# OPLSniffer.net
KiCad netlist of a schematic drawn in EAGLE
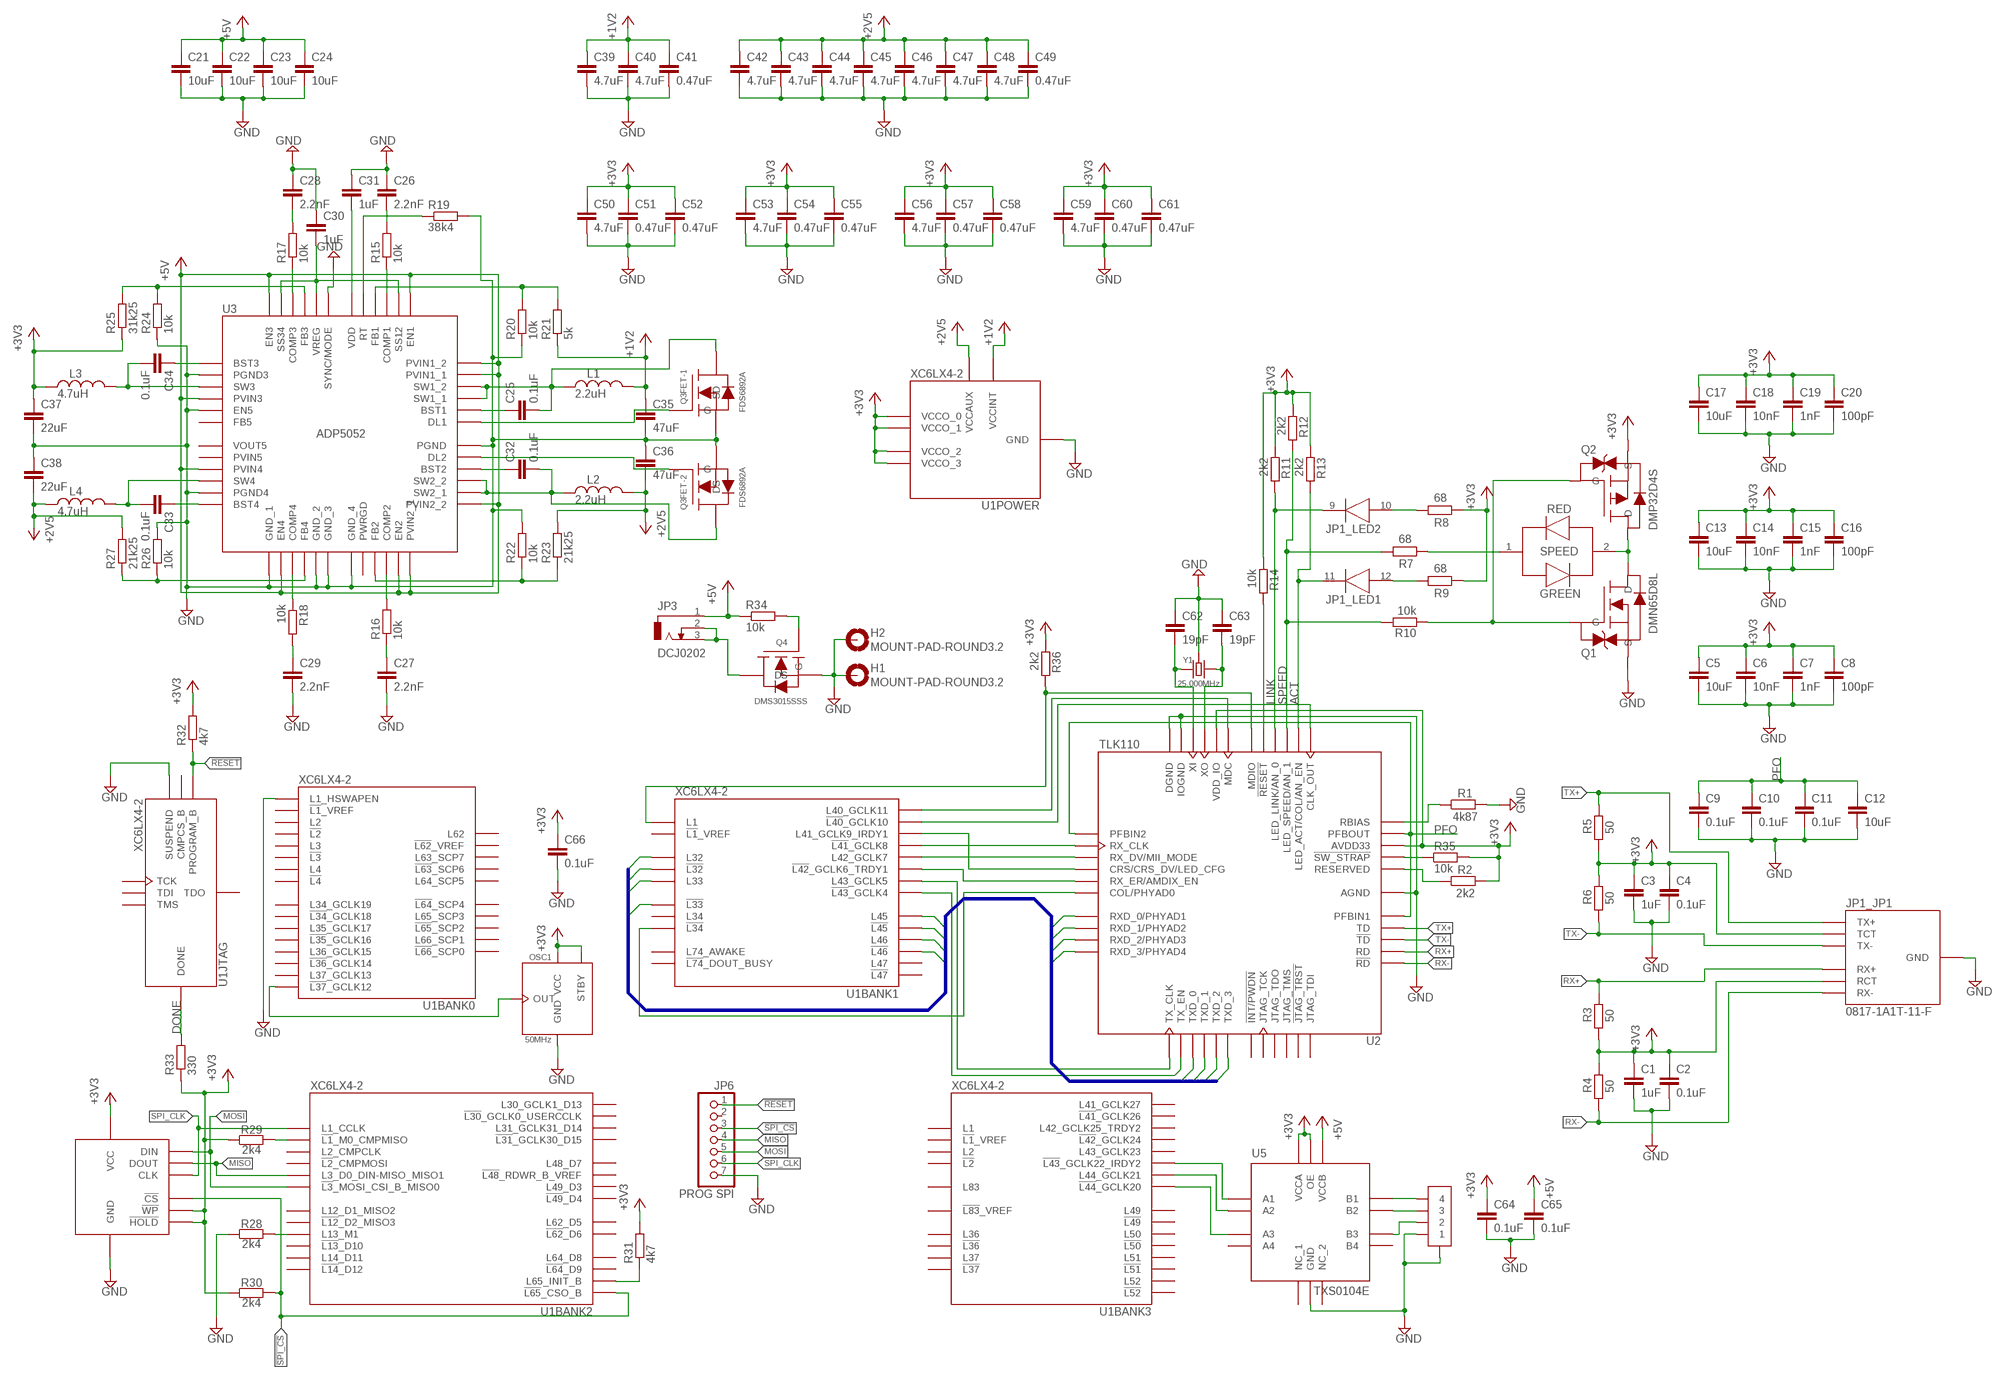
[diagram p0: schematic, sheet 1]

(export (version "E")
  (design (tool "Eeschema 10.0.6"))
  (components
    (comp (ref "C1")
      (value "1uF")
      (footprint "eagle-import:C0603K")
      (fields (field (name "MPN") "MC0603X105M6R3CT"))
      (libsource (lib "eagle-import") (part "C-EUC0603K"))
    )
    (comp (ref "C2")
      (value "0.1uF")
      (footprint "eagle-import:C0603K")
      (fields (field (name "MPN") "MC0603B104J250CT"))
      (libsource (lib "eagle-import") (part "C-EUC0603K"))
    )
    (comp (ref "C3")
      (value "1uF")
      (footprint "eagle-import:C0603K")
      (fields (field (name "MPN") "MC0603X105M6R3CT"))
      (libsource (lib "eagle-import") (part "C-EUC0603K"))
    )
    (comp (ref "C4")
      (value "0.1uF")
      (footprint "eagle-import:C0603K")
      (fields (field (name "MPN") "MC0603B104J250CT"))
      (libsource (lib "eagle-import") (part "C-EUC0603K"))
    )
    (comp (ref "C5")
      (value "10uF")
      (footprint "eagle-import:C0805K")
      (fields (field (name "MPN") "MC0805X106K250CT"))
      (libsource (lib "eagle-import") (part "C-EUC0805K"))
    )
    (comp (ref "C6")
      (value "10nF")
      (footprint "eagle-import:C0603K")
      (fields (field (name "MPN") "MCCA000238"))
      (libsource (lib "eagle-import") (part "C-EUC0603K"))
    )
    (comp (ref "C7")
      (value "1nF")
      (footprint "eagle-import:C0603K")
      (fields (field (name "MPN") "MC0603B102K500CT"))
      (libsource (lib "eagle-import") (part "C-EUC0603K"))
    )
    (comp (ref "C8")
      (value "100pF")
      (footprint "eagle-import:C0603K")
      (fields (field (name "MPN") "MCCA001175"))
      (libsource (lib "eagle-import") (part "C-EUC0603K"))
    )
    (comp (ref "C9")
      (value "0.1uF")
      (footprint "eagle-import:C0603K")
      (fields (field (name "MPN") "MC0603B104J250CT"))
      (libsource (lib "eagle-import") (part "C-EUC0603K"))
    )
    (comp (ref "C10")
      (value "0.1uF")
      (footprint "eagle-import:C0603K")
      (fields (field (name "MPN") "MC0603B104J250CT"))
      (libsource (lib "eagle-import") (part "C-EUC0603K"))
    )
    (comp (ref "C11")
      (value "0.1uF")
      (footprint "eagle-import:C0603K")
      (fields (field (name "MPN") "MC0603B104J250CT"))
      (libsource (lib "eagle-import") (part "C-EUC0603K"))
    )
    (comp (ref "C12")
      (value "10uF")
      (footprint "eagle-import:C0805K")
      (fields (field (name "MPN") "MC0805X106K250CT"))
      (libsource (lib "eagle-import") (part "C-EUC0805K"))
    )
    (comp (ref "C13")
      (value "10uF")
      (footprint "eagle-import:C0805K")
      (fields (field (name "MPN") "MC0805X106K250CT"))
      (libsource (lib "eagle-import") (part "C-EUC0805K"))
    )
    (comp (ref "C14")
      (value "10nF")
      (footprint "eagle-import:C0603K")
      (fields (field (name "MPN") "MCCA000238"))
      (libsource (lib "eagle-import") (part "C-EUC0603K"))
    )
    (comp (ref "C15")
      (value "1nF")
      (footprint "eagle-import:C0603K")
      (fields (field (name "MPN") "MC0603B102K500CT"))
      (libsource (lib "eagle-import") (part "C-EUC0603K"))
    )
    (comp (ref "C16")
      (value "100pF")
      (footprint "eagle-import:C0603K")
      (fields (field (name "MPN") "MCCA001175"))
      (libsource (lib "eagle-import") (part "C-EUC0603K"))
    )
    (comp (ref "C17")
      (value "10uF")
      (footprint "eagle-import:C0805K")
      (fields (field (name "MPN") "MC0805X106K250CT"))
      (libsource (lib "eagle-import") (part "C-EUC0805K"))
    )
    (comp (ref "C18")
      (value "10nF")
      (footprint "eagle-import:C0603K")
      (fields (field (name "MPN") "MCCA000238"))
      (libsource (lib "eagle-import") (part "C-EUC0603K"))
    )
    (comp (ref "C19")
      (value "1nF")
      (footprint "eagle-import:C0603K")
      (fields (field (name "MPN") "MC0603B102K500CT"))
      (libsource (lib "eagle-import") (part "C-EUC0603K"))
    )
    (comp (ref "C20")
      (value "100pF")
      (footprint "eagle-import:C0603K")
      (fields (field (name "MPN") "MCCA001175"))
      (libsource (lib "eagle-import") (part "C-EUC0603K"))
    )
    (comp (ref "C21")
      (value "10uF")
      (footprint "eagle-import:C0805K")
      (fields (field (name "MPN") "GRM21BR61E106KA73L"))
      (libsource (lib "eagle-import") (part "C-EUC0805K"))
    )
    (comp (ref "C22")
      (value "10uF")
      (footprint "eagle-import:C0805K")
      (fields (field (name "MPN") "MC0805X106K250CT"))
      (libsource (lib "eagle-import") (part "C-EUC0805K"))
    )
    (comp (ref "C23")
      (value "10uF")
      (footprint "eagle-import:C0805K")
      (fields (field (name "MPN") "MC0805X106K250CT"))
      (libsource (lib "eagle-import") (part "C-EUC0805K"))
    )
    (comp (ref "C24")
      (value "10uF")
      (footprint "eagle-import:C0805K")
      (fields (field (name "MPN") "MC0805X106K250CT"))
      (libsource (lib "eagle-import") (part "C-EUC0805K"))
    )
    (comp (ref "C25")
      (value "0.1uF")
      (footprint "eagle-import:C0603K")
      (fields (field (name "MPN") "MC0603B104J250CT"))
      (libsource (lib "eagle-import") (part "C-EUC0603K"))
    )
    (comp (ref "C26")
      (value "2.2nF")
      (footprint "eagle-import:C0603K")
      (fields (field (name "MPN") "MCCA001160"))
      (libsource (lib "eagle-import") (part "C-EUC0603K"))
    )
    (comp (ref "C27")
      (value "2.2nF")
      (footprint "eagle-import:C0603K")
      (fields (field (name "MPN") "MCCA001160"))
      (libsource (lib "eagle-import") (part "C-EUC0603K"))
    )
    (comp (ref "C28")
      (value "2.2nF")
      (footprint "eagle-import:C0603K")
      (fields (field (name "MPN") "MCCA001160"))
      (libsource (lib "eagle-import") (part "C-EUC0603K"))
    )
    (comp (ref "C29")
      (value "2.2nF")
      (footprint "eagle-import:C0603K")
      (fields (field (name "MPN") "MCCA001160"))
      (libsource (lib "eagle-import") (part "C-EUC0603K"))
    )
    (comp (ref "C30")
      (value "1uF")
      (footprint "eagle-import:C0603K")
      (fields (field (name "MPN") "MC0603X105M6R3CT"))
      (libsource (lib "eagle-import") (part "C-EUC0603K"))
    )
    (comp (ref "C31")
      (value "1uF")
      (footprint "eagle-import:C0603K")
      (fields (field (name "MPN") "MC0603X105M6R3CT"))
      (libsource (lib "eagle-import") (part "C-EUC0603K"))
    )
    (comp (ref "C32")
      (value "0.1uF")
      (footprint "eagle-import:C0603K")
      (fields (field (name "MPN") "MC0603B104J250CT"))
      (libsource (lib "eagle-import") (part "C-EUC0603K"))
    )
    (comp (ref "C33")
      (value "0.1uF")
      (footprint "eagle-import:C0603K")
      (fields (field (name "MPN") "MC0603B104J250CT"))
      (libsource (lib "eagle-import") (part "C-EUC0603K"))
    )
    (comp (ref "C34")
      (value "0.1uF")
      (footprint "eagle-import:C0603K")
      (fields (field (name "MPN") "MC0603B104J250CT"))
      (libsource (lib "eagle-import") (part "C-EUC0603K"))
    )
    (comp (ref "C35")
      (value "47uF")
      (footprint "eagle-import:C1206K")
      (fields (field (name "MPN") "GRM31CR60J476KE19L"))
      (libsource (lib "eagle-import") (part "C-EUC1206K"))
    )
    (comp (ref "C36")
      (value "47uF")
      (footprint "eagle-import:C1206K")
      (fields (field (name "MPN") "GRM31CR60J476KE19L"))
      (libsource (lib "eagle-import") (part "C-EUC1206K"))
    )
    (comp (ref "C37")
      (value "22uF")
      (footprint "eagle-import:C0805K")
      (fields (field (name "MPN") "C0805C226M9PACTU"))
      (libsource (lib "eagle-import") (part "C-EUC0805K"))
    )
    (comp (ref "C38")
      (value "22uF")
      (footprint "eagle-import:C0805K")
      (fields (field (name "MPN") "C0805C226M9PACTU"))
      (libsource (lib "eagle-import") (part "C-EUC0805K"))
    )
    (comp (ref "C39")
      (value "4.7uF")
      (footprint "eagle-import:C0603K")
      (fields (field (name "MPN") "MC0603X475K6R3CT"))
      (libsource (lib "eagle-import") (part "C-EUC0603K"))
    )
    (comp (ref "C40")
      (value "4.7uF")
      (footprint "eagle-import:C0603K")
      (fields (field (name "MPN") "MC0603X475K6R3CT"))
      (libsource (lib "eagle-import") (part "C-EUC0603K"))
    )
    (comp (ref "C41")
      (value "0.47uF")
      (footprint "eagle-import:C0603K")
      (fields (field (name "MPN") "MC0603X474K100CT"))
      (libsource (lib "eagle-import") (part "C-EUC0603K"))
    )
    (comp (ref "C42")
      (value "4.7uF")
      (footprint "eagle-import:C0603K")
      (fields (field (name "MPN") "MC0603X475K6R3CT"))
      (libsource (lib "eagle-import") (part "C-EUC0603K"))
    )
    (comp (ref "C43")
      (value "4.7uF")
      (footprint "eagle-import:C0603K")
      (fields (field (name "MPN") "MC0603X475K6R3CT"))
      (libsource (lib "eagle-import") (part "C-EUC0603K"))
    )
    (comp (ref "C44")
      (value "4.7uF")
      (footprint "eagle-import:C0603K")
      (fields (field (name "MPN") "MC0603X475K6R3CT"))
      (libsource (lib "eagle-import") (part "C-EUC0603K"))
    )
    (comp (ref "C45")
      (value "4.7uF")
      (footprint "eagle-import:C0603K")
      (fields (field (name "MPN") "MC0603X475K6R3CT"))
      (libsource (lib "eagle-import") (part "C-EUC0603K"))
    )
    (comp (ref "C46")
      (value "4.7uF")
      (footprint "eagle-import:C0603K")
      (fields (field (name "MPN") "MC0603X475K6R3CT"))
      (libsource (lib "eagle-import") (part "C-EUC0603K"))
    )
    (comp (ref "C47")
      (value "4.7uF")
      (footprint "eagle-import:C0603K")
      (fields (field (name "MPN") "MC0603X475K6R3CT"))
      (libsource (lib "eagle-import") (part "C-EUC0603K"))
    )
    (comp (ref "C48")
      (value "4.7uF")
      (footprint "eagle-import:C0603K")
      (fields (field (name "MPN") "MC0603X475K6R3CT"))
      (libsource (lib "eagle-import") (part "C-EUC0603K"))
    )
    (comp (ref "C49")
      (value "0.47uF")
      (footprint "eagle-import:C0603K")
      (fields (field (name "MPN") "MC0603X474K100CT"))
      (libsource (lib "eagle-import") (part "C-EUC0603K"))
    )
    (comp (ref "C50")
      (value "4.7uF")
      (footprint "eagle-import:C0603K")
      (fields (field (name "MPN") "MC0603X475K6R3CT"))
      (libsource (lib "eagle-import") (part "C-EUC0603K"))
    )
    (comp (ref "C51")
      (value "0.47uF")
      (footprint "eagle-import:C0603K")
      (fields (field (name "MPN") "MC0603X474K100CT"))
      (libsource (lib "eagle-import") (part "C-EUC0603K"))
    )
    (comp (ref "C52")
      (value "0.47uF")
      (footprint "eagle-import:C0603K")
      (fields (field (name "MPN") "MC0603X474K100CT"))
      (libsource (lib "eagle-import") (part "C-EUC0603K"))
    )
    (comp (ref "C53")
      (value "4.7uF")
      (footprint "eagle-import:C0603K")
      (fields (field (name "MPN") "MC0603X475K6R3CT"))
      (libsource (lib "eagle-import") (part "C-EUC0603K"))
    )
    (comp (ref "C54")
      (value "0.47uF")
      (footprint "eagle-import:C0603K")
      (fields (field (name "MPN") "MC0603X474K100CT"))
      (libsource (lib "eagle-import") (part "C-EUC0603K"))
    )
    (comp (ref "C55")
      (value "0.47uF")
      (footprint "eagle-import:C0603K")
      (fields (field (name "MPN") "MC0603X474K100CT"))
      (libsource (lib "eagle-import") (part "C-EUC0603K"))
    )
    (comp (ref "C56")
      (value "4.7uF")
      (footprint "eagle-import:C0603K")
      (fields (field (name "MPN") "MC0603X475K6R3CT"))
      (libsource (lib "eagle-import") (part "C-EUC0603K"))
    )
    (comp (ref "C57")
      (value "0.47uF")
      (footprint "eagle-import:C0603K")
      (fields (field (name "MPN") "MC0603X474K100CT"))
      (libsource (lib "eagle-import") (part "C-EUC0603K"))
    )
    (comp (ref "C58")
      (value "0.47uF")
      (footprint "eagle-import:C0603K")
      (fields (field (name "MPN") "MC0603X474K100CT"))
      (libsource (lib "eagle-import") (part "C-EUC0603K"))
    )
    (comp (ref "C59")
      (value "4.7uF")
      (footprint "eagle-import:C0603K")
      (fields (field (name "MPN") "MC0603X475K6R3CT"))
      (libsource (lib "eagle-import") (part "C-EUC0603K"))
    )
    (comp (ref "C60")
      (value "0.47uF")
      (footprint "eagle-import:C0603K")
      (fields (field (name "MPN") "MC0603X474K100CT"))
      (libsource (lib "eagle-import") (part "C-EUC0603K"))
    )
    (comp (ref "C61")
      (value "0.47uF")
      (footprint "eagle-import:C0603K")
      (fields (field (name "MPN") "MC0603X474K100CT"))
      (libsource (lib "eagle-import") (part "C-EUC0603K"))
    )
    (comp (ref "C62")
      (value "19pF")
      (footprint "eagle-import:C0603K")
      (fields (field (name "MFR") "Kemet") (field (name "MPN") "C0603C180J5GACTU"))
      (libsource (lib "eagle-import") (part "C-EUC0603K"))
    )
    (comp (ref "C63")
      (value "19pF")
      (footprint "eagle-import:C0603K")
      (fields (field (name "MFR") "Kemet") (field (name "MPN") "C0603C180J5GACTU"))
      (libsource (lib "eagle-import") (part "C-EUC0603K"))
    )
    (comp (ref "C64")
      (value "0.1uF")
      (footprint "eagle-import:C0603K")
      (fields (field (name "MPN") "MC0603B104J250CT"))
      (libsource (lib "eagle-import") (part "C-EUC0603K"))
    )
    (comp (ref "C65")
      (value "0.1uF")
      (footprint "eagle-import:C0603K")
      (fields (field (name "MPN") "MC0603B104J250CT"))
      (libsource (lib "eagle-import") (part "C-EUC0603K"))
    )
    (comp (ref "C66")
      (value "0.1uF")
      (footprint "eagle-import:C0603K")
      (fields (field (name "MPN") "MC0603B104J250CT"))
      (libsource (lib "eagle-import") (part "C-EUC0603K"))
    )
    (comp (ref "H1")
      (value "MOUNT-PAD-ROUND3.2")
      (footprint "eagle-import:3,2-PAD")
      (libsource (lib "eagle-import") (part "MOUNT-PAD-ROUND3.2"))
    )
    (comp (ref "H2")
      (value "MOUNT-PAD-ROUND3.2")
      (footprint "eagle-import:3,2-PAD")
      (libsource (lib "eagle-import") (part "MOUNT-PAD-ROUND3.2"))
    )
    (comp (ref "JP1")
      (value "0817-1A1T-11-F")
      (footprint "eagle-import:0817-1A1T-11-F")
      (fields (field (name "MPN") "0817-1A1T-11-F") (field (name "OC_DIGIKEY") "507-1423-ND"))
      (libsource (lib "eagle-import") (part "0817-1A1T-11-F"))
    )
    (comp (ref "JP3")
      (value "DCJ0202")
      (footprint "eagle-import:DCJ0202")
      (libsource (lib "eagle-import") (part "DCJ0202"))
    )
    (comp (ref "JP4")
      (value "OPL2")
      (footprint "eagle-import:53261-0471_PICOBLADE")
      (fields (field (name "MFR") "Molex") (field (name "MPN") "53261-0471"))
      (libsource (lib "eagle-import") (part "4PIN_PICOBLADE53261-047153261-0471"))
    )
    (comp (ref "JP6")
      (value "PROG SPI")
      (footprint "eagle-import:PINHEAD_1X7")
      (libsource (lib "eagle-import") (part "PINHEAD_1X7"))
    )
    (comp (ref "L1")
      (value "2.2uH")
      (footprint "eagle-import:NRS4018")
      (fields (field (name "MPN") "NRS4018T2R2MDGJ"))
      (libsource (lib "eagle-import") (part "INDUCTOR"))
    )
    (comp (ref "L2")
      (value "2.2uH")
      (footprint "eagle-import:NRS4018")
      (fields (field (name "MPN") "NRS4018T2R2MDGJ"))
      (libsource (lib "eagle-import") (part "INDUCTOR"))
    )
    (comp (ref "L3")
      (value "4.7uH")
      (footprint "eagle-import:NRS4018")
      (fields (field (name "MPN") "NRS4018T4R7MDGJ"))
      (libsource (lib "eagle-import") (part "INDUCTOR"))
    )
    (comp (ref "L4")
      (value "4.7uH")
      (footprint "eagle-import:NRS4018")
      (fields (field (name "MPN") "NRS4018T4R7MDGJ"))
      (libsource (lib "eagle-import") (part "INDUCTOR"))
    )
    (comp (ref "OSC1")
      (value "50MHz")
      (footprint "eagle-import:SMD3225")
      (fields (field (name "MFR") "Abracon") (field (name "MPN") "ASE-50.000MHZ-L-R-T"))
      (libsource (lib "eagle-import") (part "OSC3225"))
    )
    (comp (ref "Q1")
      (value "DMN65D8L")
      (footprint "eagle-import:SOT23")
      (libsource (lib "eagle-import") (part "DMN65D8L"))
    )
    (comp (ref "Q2")
      (value "DMP32D4S")
      (footprint "eagle-import:SOT23")
      (fields (field (name "MPN") "DMP32D4S-13"))
      (libsource (lib "eagle-import") (part "DMP32D4S"))
    )
    (comp (ref "Q3")
      (value "FDS6892A")
      (footprint "eagle-import:SOIC8")
      (libsource (lib "eagle-import") (part "FDS6892A"))
    )
    (comp (ref "Q4")
      (value "DMS3015SSS")
      (footprint "eagle-import:SOIC8")
      (libsource (lib "eagle-import") (part "DMS3015SSS"))
    )
    (comp (ref "R1")
      (value "4k87")
      (footprint "eagle-import:R0603")
      (fields (field (name "MPN") "CRCW06034K87FKEA"))
      (libsource (lib "eagle-import") (part "R-EU_R0603"))
    )
    (comp (ref "R2")
      (value "2k2")
      (footprint "eagle-import:R0603")
      (fields (field (name "MPN") "MCMR06X2201FTL"))
      (libsource (lib "eagle-import") (part "R-EU_R0603"))
    )
    (comp (ref "R3")
      (value "50")
      (footprint "eagle-import:R0603")
      (fields (field (name "MPN") "CRCW060350R0FKEA"))
      (libsource (lib "eagle-import") (part "R-EU_R0603"))
    )
    (comp (ref "R4")
      (value "50")
      (footprint "eagle-import:R0603")
      (fields (field (name "MPN") "CRCW060350R0FKEA"))
      (libsource (lib "eagle-import") (part "R-EU_R0603"))
    )
    (comp (ref "R5")
      (value "50")
      (footprint "eagle-import:R0603")
      (fields (field (name "MPN") "CRCW060350R0FKEA"))
      (libsource (lib "eagle-import") (part "R-EU_R0603"))
    )
    (comp (ref "R6")
      (value "50")
      (footprint "eagle-import:R0603")
      (fields (field (name "MPN") "CRCW060350R0FKEA"))
      (libsource (lib "eagle-import") (part "R-EU_R0603"))
    )
    (comp (ref "R7")
      (value "68")
      (footprint "eagle-import:R0603")
      (fields (field (name "MPN") "MCMR06X68R0FTL"))
      (libsource (lib "eagle-import") (part "R-EU_R0603"))
    )
    (comp (ref "R8")
      (value "68")
      (footprint "eagle-import:R0603")
      (fields (field (name "MPN") "MCMR06X68R0FTL"))
      (libsource (lib "eagle-import") (part "R-EU_R0603"))
    )
    (comp (ref "R9")
      (value "68")
      (footprint "eagle-import:R0603")
      (fields (field (name "MPN") "MCMR06X68R0FTL"))
      (libsource (lib "eagle-import") (part "R-EU_R0603"))
    )
    (comp (ref "R10")
      (value "10k")
      (footprint "eagle-import:R0603")
      (fields (field (name "MPN") "MC0063W0603110K"))
      (libsource (lib "eagle-import") (part "R-EU_R0603"))
    )
    (comp (ref "R11")
      (value "2k2")
      (footprint "eagle-import:R0603")
      (fields (field (name "MPN") "MCMR06X2201FTL"))
      (libsource (lib "eagle-import") (part "R-EU_R0603"))
    )
    (comp (ref "R12")
      (value "2k2")
      (footprint "eagle-import:R0603")
      (fields (field (name "MPN") "MCMR06X2201FTL"))
      (libsource (lib "eagle-import") (part "R-EU_R0603"))
    )
    (comp (ref "R13")
      (value "2k2")
      (footprint "eagle-import:R0603")
      (fields (field (name "MPN") "MCMR06X2201FTL"))
      (libsource (lib "eagle-import") (part "R-EU_R0603"))
    )
    (comp (ref "R14")
      (value "10k")
      (footprint "eagle-import:R0603")
      (fields (field (name "MPN") "MC0063W0603110K"))
      (libsource (lib "eagle-import") (part "R-EU_R0603"))
    )
    (comp (ref "R15")
      (value "10k")
      (footprint "eagle-import:R0603")
      (fields (field (name "MPN") "MC0063W0603110K"))
      (libsource (lib "eagle-import") (part "R-EU_R0603"))
    )
    (comp (ref "R16")
      (value "10k")
      (footprint "eagle-import:R0603")
      (fields (field (name "MPN") "MC0063W0603110K"))
      (libsource (lib "eagle-import") (part "R-EU_R0603"))
    )
    (comp (ref "R17")
      (value "10k")
      (footprint "eagle-import:R0603")
      (fields (field (name "MPN") "MC0063W0603110K"))
      (libsource (lib "eagle-import") (part "R-EU_R0603"))
    )
    (comp (ref "R18")
      (value "10k")
      (footprint "eagle-import:R0603")
      (fields (field (name "MPN") "MC0063W0603110K"))
      (libsource (lib "eagle-import") (part "R-EU_R0603"))
    )
    (comp (ref "R19")
      (value "38k4")
      (footprint "eagle-import:R0603")
      (fields (field (name "MPN") "CRCW060338K3FKEA"))
      (libsource (lib "eagle-import") (part "R-EU_R0603"))
    )
    (comp (ref "R20")
      (value "10k")
      (footprint "eagle-import:R0603")
      (fields (field (name "MPN") "MC0063W0603110K"))
      (libsource (lib "eagle-import") (part "R-EU_R0603"))
    )
    (comp (ref "R21")
      (value "5k")
      (footprint "eagle-import:R0603")
      (fields (field (name "MPN") "MC0063W060314K99"))
      (libsource (lib "eagle-import") (part "R-EU_R0603"))
    )
    (comp (ref "R22")
      (value "10k")
      (footprint "eagle-import:R0603")
      (fields (field (name "MPN") "MC0063W0603110K"))
      (libsource (lib "eagle-import") (part "R-EU_R0603"))
    )
    (comp (ref "R23")
      (value "21k25")
      (footprint "eagle-import:R0603")
      (fields (field (name "MPN") "MC0063W0603121K5"))
      (libsource (lib "eagle-import") (part "R-EU_R0603"))
    )
    (comp (ref "R24")
      (value "10k")
      (footprint "eagle-import:R0603")
      (fields (field (name "MPN") "MC0063W0603110K"))
      (libsource (lib "eagle-import") (part "R-EU_R0603"))
    )
    (comp (ref "R25")
      (value "31k25")
      (footprint "eagle-import:R0603")
      (fields (field (name "MPN") "CRCW060331K6FKEA"))
      (libsource (lib "eagle-import") (part "R-EU_R0603"))
    )
    (comp (ref "R26")
      (value "10k")
      (footprint "eagle-import:R0603")
      (fields (field (name "MPN") "MC0063W0603110K"))
      (libsource (lib "eagle-import") (part "R-EU_R0603"))
    )
    (comp (ref "R27")
      (value "21k25")
      (footprint "eagle-import:R0603")
      (fields (field (name "MPN") "MC0063W0603121K5"))
      (libsource (lib "eagle-import") (part "R-EU_R0603"))
    )
    (comp (ref "R28")
      (value "2k4")
      (footprint "eagle-import:R0603")
      (fields (field (name "MPN") "MCMR06X2401FTL"))
      (libsource (lib "eagle-import") (part "R-EU_R0603"))
    )
    (comp (ref "R29")
      (value "2k4")
      (footprint "eagle-import:R0603")
      (fields (field (name "MPN") "MCMR06X2401FTL"))
      (libsource (lib "eagle-import") (part "R-EU_R0603"))
    )
    (comp (ref "R30")
      (value "2k4")
      (footprint "eagle-import:R0603")
      (fields (field (name "MPN") "MCMR06X2401FTL"))
      (libsource (lib "eagle-import") (part "R-EU_R0603"))
    )
    (comp (ref "R31")
      (value "4k7")
      (footprint "eagle-import:R0603")
      (fields (field (name "MPN") "MCMR06X4701FTL"))
      (libsource (lib "eagle-import") (part "R-EU_R0603"))
    )
    (comp (ref "R32")
      (value "4k7")
      (footprint "eagle-import:R0603")
      (fields (field (name "MPN") "MCMR06X4701FTL"))
      (libsource (lib "eagle-import") (part "R-EU_R0603"))
    )
    (comp (ref "R33")
      (value "330")
      (footprint "eagle-import:R0603")
      (fields (field (name "MPN") "MCMR06X3300FTL"))
      (libsource (lib "eagle-import") (part "R-EU_R0603"))
    )
    (comp (ref "R34")
      (value "10k")
      (footprint "eagle-import:R0603")
      (fields (field (name "MPN") "MC0063W0603110K"))
      (libsource (lib "eagle-import") (part "R-EU_R0603"))
    )
    (comp (ref "R35")
      (value "10k")
      (footprint "eagle-import:R0603")
      (fields (field (name "MPN") "MC0063W0603110K"))
      (libsource (lib "eagle-import") (part "R-EU_R0603"))
    )
    (comp (ref "R36")
      (value "2k2")
      (footprint "eagle-import:R0603")
      (fields (field (name "MPN") "MCMR06X2201FTL"))
      (libsource (lib "eagle-import") (part "R-EU_R0603"))
    )
    (comp (ref "SPEED")
      (value "RG-LED")
      (footprint "eagle-import:CHIPLED_0805")
      (fields (field (name "MPN") "KPB-2012SURKCGKC"))
      (libsource (lib "eagle-import") (part "RG-LED"))
    )
    (comp (ref "U1")
      (value "XC6LX4-2")
      (footprint "eagle-import:TQFP144")
      (fields (field (name "MPN") "XC6SLX4-2TQG144C"))
      (libsource (lib "eagle-import") (part "XC6LX4-2"))
    )
    (comp (ref "U2")
      (value "TLK110")
      (footprint "eagle-import:LQFP48")
      (fields (field (name "MPN") "TLK110PTR"))
      (libsource (lib "eagle-import") (part "TLK110"))
    )
    (comp (ref "U3")
      (value "ADP5052")
      (footprint "eagle-import:LFSCP48")
      (fields (field (name "MPN") "ADP5052ACPZ-R7"))
      (libsource (lib "eagle-import") (part "ADP5052"))
    )
    (comp (ref "U4")
      (value "M25P16-VMN6P")
      (footprint "eagle-import:SOIC8")
      (libsource (lib "eagle-import") (part "M25P16-VMN6P"))
    )
    (comp (ref "U5")
      (value "TXS0104E")
      (footprint "eagle-import:TSSOP14")
      (libsource (lib "eagle-import") (part "TXS0104E"))
    )
    (comp (ref "Y1")
      (value "25.000MHz")
      (footprint "eagle-import:SMD3225")
      (fields (field (name "MFR") "Multicomp") (field (name "MPN") "MCSJK-7U-25.00-12-10-60-B-10"))
      (libsource (lib "eagle-import") (part "CRYSTAL_GND3225"))
    )
  )
  (nets
    (net (code "1") (name "+1V2") (class "Default")
      (node (ref "C35") (pin "1") (pinfunction "1_1") (pintype "passive"))
      (node (ref "C39") (pin "1") (pinfunction "1_1") (pintype "passive"))
      (node (ref "C40") (pin "1") (pinfunction "1_1") (pintype "passive"))
      (node (ref "C41") (pin "1") (pinfunction "1_1") (pintype "passive"))
      (node (ref "L1") (pin "2") (pinfunction "2_2") (pintype "passive"))
      (node (ref "R21") (pin "1") (pinfunction "1_1") (pintype "passive"))
      (node (ref "U1") (pin "128") (pinfunction "VCCINT_128") (pintype "power_in"))
      (node (ref "U1") (pin "19") (pinfunction "VCCINT_19") (pintype "power_in"))
      (node (ref "U1") (pin "28") (pinfunction "VCCINT_28") (pintype "power_in"))
      (node (ref "U1") (pin "52") (pinfunction "VCCINT_52") (pintype "power_in"))
      (node (ref "U1") (pin "89") (pinfunction "VCCINT_89") (pintype "power_in"))
    )
    (net (code "2") (name "+2V5") (class "Default")
      (node (ref "C36") (pin "2") (pinfunction "2_2") (pintype "passive"))
      (node (ref "C38") (pin "2") (pinfunction "2_2") (pintype "passive"))
      (node (ref "C42") (pin "1") (pinfunction "1_1") (pintype "passive"))
      (node (ref "C43") (pin "1") (pinfunction "1_1") (pintype "passive"))
      (node (ref "C44") (pin "1") (pinfunction "1_1") (pintype "passive"))
      (node (ref "C45") (pin "1") (pinfunction "1_1") (pintype "passive"))
      (node (ref "C46") (pin "1") (pinfunction "1_1") (pintype "passive"))
      (node (ref "C47") (pin "1") (pinfunction "1_1") (pintype "passive"))
      (node (ref "C48") (pin "1") (pinfunction "1_1") (pintype "passive"))
      (node (ref "C49") (pin "1") (pinfunction "1_1") (pintype "passive"))
      (node (ref "L2") (pin "2") (pinfunction "2_2") (pintype "passive"))
      (node (ref "L4") (pin "1") (pinfunction "1_1") (pintype "passive"))
      (node (ref "R23") (pin "2") (pinfunction "2_2") (pintype "passive"))
      (node (ref "R27") (pin "2") (pinfunction "2_2") (pintype "passive"))
      (node (ref "U1") (pin "129") (pinfunction "VCCAUX_129") (pintype "power_in"))
      (node (ref "U1") (pin "20") (pinfunction "VCCAUX_20") (pintype "power_in"))
      (node (ref "U1") (pin "36") (pinfunction "VCCAUX_36") (pintype "power_in"))
      (node (ref "U1") (pin "53") (pinfunction "VCCAUX_53") (pintype "power_in"))
      (node (ref "U1") (pin "90") (pinfunction "VCCAUX_90") (pintype "power_in"))
    )
    (net (code "3") (name "+3V3") (class "Default")
      (node (ref "C1") (pin "1") (pinfunction "1_1") (pintype "passive"))
      (node (ref "C13") (pin "1") (pinfunction "1_1") (pintype "passive"))
      (node (ref "C14") (pin "1") (pinfunction "1_1") (pintype "passive"))
      (node (ref "C15") (pin "1") (pinfunction "1_1") (pintype "passive"))
      (node (ref "C16") (pin "1") (pinfunction "1_1") (pintype "passive"))
      (node (ref "C17") (pin "1") (pinfunction "1_1") (pintype "passive"))
      (node (ref "C18") (pin "1") (pinfunction "1_1") (pintype "passive"))
      (node (ref "C19") (pin "1") (pinfunction "1_1") (pintype "passive"))
      (node (ref "C2") (pin "1") (pinfunction "1_1") (pintype "passive"))
      (node (ref "C20") (pin "1") (pinfunction "1_1") (pintype "passive"))
      (node (ref "C3") (pin "1") (pinfunction "1_1") (pintype "passive"))
      (node (ref "C37") (pin "1") (pinfunction "1_1") (pintype "passive"))
      (node (ref "C4") (pin "1") (pinfunction "1_1") (pintype "passive"))
      (node (ref "C5") (pin "1") (pinfunction "1_1") (pintype "passive"))
      (node (ref "C50") (pin "1") (pinfunction "1_1") (pintype "passive"))
      (node (ref "C51") (pin "1") (pinfunction "1_1") (pintype "passive"))
      (node (ref "C52") (pin "1") (pinfunction "1_1") (pintype "passive"))
      (node (ref "C53") (pin "1") (pinfunction "1_1") (pintype "passive"))
      (node (ref "C54") (pin "1") (pinfunction "1_1") (pintype "passive"))
      (node (ref "C55") (pin "1") (pinfunction "1_1") (pintype "passive"))
      (node (ref "C56") (pin "1") (pinfunction "1_1") (pintype "passive"))
      (node (ref "C57") (pin "1") (pinfunction "1_1") (pintype "passive"))
      (node (ref "C58") (pin "1") (pinfunction "1_1") (pintype "passive"))
      (node (ref "C59") (pin "1") (pinfunction "1_1") (pintype "passive"))
      (node (ref "C6") (pin "1") (pinfunction "1_1") (pintype "passive"))
      (node (ref "C60") (pin "1") (pinfunction "1_1") (pintype "passive"))
      (node (ref "C61") (pin "1") (pinfunction "1_1") (pintype "passive"))
      (node (ref "C64") (pin "1") (pinfunction "1_1") (pintype "passive"))
      (node (ref "C66") (pin "1") (pinfunction "1_1") (pintype "passive"))
      (node (ref "C7") (pin "1") (pinfunction "1_1") (pintype "passive"))
      (node (ref "C8") (pin "1") (pinfunction "1_1") (pintype "passive"))
      (node (ref "JP1") (pin "3") (pinfunction "TCT_3") (pintype "passive"))
      (node (ref "JP1") (pin "6") (pinfunction "RCT_6") (pintype "passive"))
      (node (ref "L3") (pin "1") (pinfunction "1_1") (pintype "passive"))
      (node (ref "OSC1") (pin "1") (pinfunction "STBY_1") (pintype "input"))
      (node (ref "OSC1") (pin "4") (pinfunction "VCC_4") (pintype "power_in"))
      (node (ref "Q2") (pin "2") (pinfunction "S_2") (pintype "bidirectional"))
      (node (ref "R11") (pin "1") (pinfunction "1_1") (pintype "passive"))
      (node (ref "R12") (pin "1") (pinfunction "1_1") (pintype "passive"))
      (node (ref "R13") (pin "1") (pinfunction "1_1") (pintype "passive"))
      (node (ref "R14") (pin "1") (pinfunction "1_1") (pintype "passive"))
      (node (ref "R2") (pin "2") (pinfunction "2_2") (pintype "passive"))
      (node (ref "R25") (pin "1") (pinfunction "1_1") (pintype "passive"))
      (node (ref "R29") (pin "1") (pinfunction "1_1") (pintype "passive"))
      (node (ref "R3") (pin "1") (pinfunction "1_1") (pintype "passive"))
      (node (ref "R30") (pin "1") (pinfunction "1_1") (pintype "passive"))
      (node (ref "R31") (pin "2") (pinfunction "2_2") (pintype "passive"))
      (node (ref "R32") (pin "2") (pinfunction "2_2") (pintype "passive"))
      (node (ref "R33") (pin "1") (pinfunction "1_1") (pintype "passive"))
      (node (ref "R35") (pin "2") (pinfunction "2_2") (pintype "passive"))
      (node (ref "R36") (pin "1") (pinfunction "1_1") (pintype "passive"))
      (node (ref "R4") (pin "2") (pinfunction "2_2") (pintype "passive"))
      (node (ref "R5") (pin "1") (pinfunction "1_1") (pintype "passive"))
      (node (ref "R6") (pin "2") (pinfunction "2_2") (pintype "passive"))
      (node (ref "R8") (pin "1") (pinfunction "1_1") (pintype "passive"))
      (node (ref "R9") (pin "1") (pinfunction "1_1") (pintype "passive"))
      (node (ref "U1") (pin "103") (pinfunction "VCCO_1_103") (pintype "power_in"))
      (node (ref "U1") (pin "122") (pinfunction "VCCO_0_122") (pintype "power_in"))
      (node (ref "U1") (pin "125") (pinfunction "VCCO_0_125") (pintype "power_in"))
      (node (ref "U1") (pin "135") (pinfunction "VCCO_0_135") (pintype "power_in"))
      (node (ref "U1") (pin "18") (pinfunction "VCCO_3_18") (pintype "power_in"))
      (node (ref "U1") (pin "31") (pinfunction "VCCO_3_31") (pintype "power_in"))
      (node (ref "U1") (pin "4") (pinfunction "VCCO_3_4") (pintype "power_in"))
      (node (ref "U1") (pin "42") (pinfunction "VCCO_2_42") (pintype "power_in"))
      (node (ref "U1") (pin "63") (pinfunction "VCCO_2_63") (pintype "power_in"))
      (node (ref "U1") (pin "76") (pinfunction "VCCO_1_76") (pintype "power_in"))
      (node (ref "U1") (pin "86") (pinfunction "VCCO_1_86") (pintype "power_in"))
      (node (ref "U2") (pin "22") (pinfunction "AVDD33_22") (pintype "power_in"))
      (node (ref "U2") (pin "32") (pinfunction "VDD_IO_32") (pintype "power_in"))
      (node (ref "U2") (pin "48") (pinfunction "VDD_IO_48") (pintype "power_in"))
      (node (ref "U4") (pin "3") (pinfunction "~{WP}_3") (pintype "input"))
      (node (ref "U4") (pin "7") (pinfunction "~{HOLD}_7") (pintype "input"))
      (node (ref "U4") (pin "8") (pinfunction "VCC_8") (pintype "power_in"))
      (node (ref "U5") (pin "1") (pinfunction "VCCA_1") (pintype "power_in"))
      (node (ref "U5") (pin "8") (pinfunction "OE_8") (pintype "input"))
    )
    (net (code "4") (name "+5V") (class "Default")
      (node (ref "C21") (pin "1") (pinfunction "1_1") (pintype "passive"))
      (node (ref "C22") (pin "1") (pinfunction "1_1") (pintype "passive"))
      (node (ref "C23") (pin "1") (pinfunction "1_1") (pintype "passive"))
      (node (ref "C24") (pin "1") (pinfunction "1_1") (pintype "passive"))
      (node (ref "C65") (pin "1") (pinfunction "1_1") (pintype "passive"))
      (node (ref "JP3") (pin "1") (pinfunction "1_1") (pintype "passive"))
      (node (ref "R34") (pin "1") (pinfunction "1_1") (pintype "passive"))
      (node (ref "U3") (pin "14") (pinfunction "EN4_14") (pintype "input"))
      (node (ref "U3") (pin "23") (pinfunction "EN2_23") (pintype "input"))
      (node (ref "U3") (pin "24") (pinfunction "PVIN2_1_24") (pintype "power_in"))
      (node (ref "U3") (pin "25") (pinfunction "PVIN2_2_25") (pintype "power_in"))
      (node (ref "U3") (pin "35") (pinfunction "PVIN1_1_35") (pintype "power_in"))
      (node (ref "U3") (pin "36") (pinfunction "PVIN1_2_36") (pintype "power_in"))
      (node (ref "U3") (pin "37") (pinfunction "EN1_37") (pintype "input"))
      (node (ref "U3") (pin "4") (pinfunction "PVIN3_4") (pintype "power_in"))
      (node (ref "U3") (pin "48") (pinfunction "EN3_48") (pintype "input"))
      (node (ref "U3") (pin "9") (pinfunction "PVIN4_9") (pintype "power_in"))
      (node (ref "U5") (pin "14") (pinfunction "VCCB_14") (pintype "power_in"))
    )
    (net (code "5") (name "/ACT") (class "Default")
      (node (ref "JP1") (pin "11") (pinfunction "C_11") (pintype "passive"))
      (node (ref "R13") (pin "2") (pinfunction "2_2") (pintype "passive"))
      (node (ref "U2") (pin "26") (pinfunction "LED_ACT/COL/AN_EN_26") (pintype "output"))
    )
    (net (code "6") (name "/DONE") (class "Default")
      (node (ref "R33") (pin "2") (pinfunction "2_2") (pintype "passive"))
      (node (ref "U1") (pin "71") (pinfunction "DONE_71") (pintype "output"))
    )
    (net (code "7") (name "/LINK") (class "Default")
      (node (ref "JP1") (pin "9") (pinfunction "C_9") (pintype "passive"))
      (node (ref "R11") (pin "2") (pinfunction "2_2") (pintype "passive"))
      (node (ref "U2") (pin "28") (pinfunction "LED_LINK/AN_0_28") (pintype "output"))
    )
    (net (code "8") (name "/PFO") (class "Default")
      (node (ref "C10") (pin "1") (pinfunction "1_1") (pintype "passive"))
      (node (ref "C11") (pin "1") (pinfunction "1_1") (pintype "passive"))
      (node (ref "C12") (pin "1") (pinfunction "1_1") (pintype "passive"))
      (node (ref "C9") (pin "1") (pinfunction "1_1") (pintype "passive"))
      (node (ref "U2") (pin "18") (pinfunction "PFBIN1_18") (pintype "input"))
      (node (ref "U2") (pin "23") (pinfunction "PFBOUT_23") (pintype "output"))
      (node (ref "U2") (pin "37") (pinfunction "PFBIN2_37") (pintype "input"))
    )
    (net (code "9") (name "/PVIN5") (class "Default")
      (node (ref "U3") (pin "8") (pinfunction "PVIN5_8") (pintype "power_in"))
    )
    (net (code "10") (name "/RXD0") (class "Default")
      (node (ref "U1") (pin "102") (pinfunction "L32_102") (pintype "bidirectional"))
      (node (ref "U2") (pin "43") (pinfunction "RXD_0/PHYAD1_43") (pintype "output"))
    )
    (net (code "11") (name "/RXD1") (class "Default")
      (node (ref "U1") (pin "101") (pinfunction "~{L32}_101") (pintype "bidirectional"))
      (node (ref "U2") (pin "44") (pinfunction "RXD_1/PHYAD2_44") (pintype "output"))
    )
    (net (code "12") (name "/RXD2") (class "Default")
      (node (ref "U1") (pin "100") (pinfunction "L33_100") (pintype "bidirectional"))
      (node (ref "U2") (pin "45") (pinfunction "RXD_2/PHYAD3_45") (pintype "output"))
    )
    (net (code "13") (name "/RXD3") (class "Default")
      (node (ref "U1") (pin "99") (pinfunction "~{L33}_99") (pintype "bidirectional"))
      (node (ref "U2") (pin "46") (pinfunction "RXD_3/PHYAD4_46") (pintype "output"))
    )
    (net (code "14") (name "/SPEED") (class "Default")
      (node (ref "R10") (pin "2") (pinfunction "2_2") (pintype "passive"))
      (node (ref "R12") (pin "2") (pinfunction "2_2") (pintype "passive"))
      (node (ref "R7") (pin "2") (pinfunction "2_2") (pintype "passive"))
      (node (ref "U2") (pin "27") (pinfunction "LED_SPEED/AN_1_27") (pintype "output"))
    )
    (net (code "15") (name "/TXD0") (class "Default")
      (node (ref "U1") (pin "83") (pinfunction "L45_83") (pintype "bidirectional"))
      (node (ref "U2") (pin "3") (pinfunction "TXD_0_3") (pintype "input"))
    )
    (net (code "16") (name "/TXD1") (class "Default")
      (node (ref "U1") (pin "82") (pinfunction "~{L45}_82") (pintype "bidirectional"))
      (node (ref "U2") (pin "4") (pinfunction "TXD_1_4") (pintype "input"))
    )
    (net (code "17") (name "/TXD2") (class "Default")
      (node (ref "U1") (pin "81") (pinfunction "L46_81") (pintype "bidirectional"))
      (node (ref "U2") (pin "5") (pinfunction "TXD_2_5") (pintype "input"))
    )
    (net (code "18") (name "/TXD3") (class "Default")
      (node (ref "U1") (pin "80") (pinfunction "~{L46}_80") (pintype "bidirectional"))
      (node (ref "U2") (pin "6") (pinfunction "TXD_3_6") (pintype "input"))
    )
    (net (code "19") (name "/VOUT5") (class "Default")
      (node (ref "U3") (pin "7") (pinfunction "VOUT5_7") (pintype "power_in"))
    )
    (net (code "20") (name "/~{RESET}") (class "Default")
      (node (ref "JP6") (pin "1") (pinfunction "1_1") (pintype "passive"))
      (node (ref "R32") (pin "1") (pinfunction "1_1") (pintype "passive"))
      (node (ref "U1") (pin "37") (pinfunction "PROGRAM_B_37") (pintype "input"))
    )
    (net (code "21") (name "/~{SPI_CS}") (class "Default")
      (node (ref "JP6") (pin "3") (pinfunction "3_3") (pintype "passive"))
      (node (ref "R30") (pin "2") (pinfunction "2_2") (pintype "passive"))
      (node (ref "U1") (pin "38") (pinfunction "~{L65}_CSO_B_38") (pintype "bidirectional"))
      (node (ref "U4") (pin "1") (pinfunction "~{CS}_1") (pintype "input"))
    )
    (net (code "22") (name "GND") (class "Default")
      (node (ref "C1") (pin "2") (pinfunction "2_2") (pintype "passive"))
      (node (ref "C10") (pin "2") (pinfunction "2_2") (pintype "passive"))
      (node (ref "C11") (pin "2") (pinfunction "2_2") (pintype "passive"))
      (node (ref "C12") (pin "2") (pinfunction "2_2") (pintype "passive"))
      (node (ref "C13") (pin "2") (pinfunction "2_2") (pintype "passive"))
      (node (ref "C14") (pin "2") (pinfunction "2_2") (pintype "passive"))
      (node (ref "C15") (pin "2") (pinfunction "2_2") (pintype "passive"))
      (node (ref "C16") (pin "2") (pinfunction "2_2") (pintype "passive"))
      (node (ref "C17") (pin "2") (pinfunction "2_2") (pintype "passive"))
      (node (ref "C18") (pin "2") (pinfunction "2_2") (pintype "passive"))
      (node (ref "C19") (pin "2") (pinfunction "2_2") (pintype "passive"))
      (node (ref "C2") (pin "2") (pinfunction "2_2") (pintype "passive"))
      (node (ref "C20") (pin "2") (pinfunction "2_2") (pintype "passive"))
      (node (ref "C21") (pin "2") (pinfunction "2_2") (pintype "passive"))
      (node (ref "C22") (pin "2") (pinfunction "2_2") (pintype "passive"))
      (node (ref "C23") (pin "2") (pinfunction "2_2") (pintype "passive"))
      (node (ref "C24") (pin "2") (pinfunction "2_2") (pintype "passive"))
      (node (ref "C26") (pin "1") (pinfunction "1_1") (pintype "passive"))
      (node (ref "C27") (pin "2") (pinfunction "2_2") (pintype "passive"))
      (node (ref "C28") (pin "1") (pinfunction "1_1") (pintype "passive"))
      (node (ref "C29") (pin "2") (pinfunction "2_2") (pintype "passive"))
      (node (ref "C3") (pin "2") (pinfunction "2_2") (pintype "passive"))
      (node (ref "C30") (pin "1") (pinfunction "1_1") (pintype "passive"))
      (node (ref "C31") (pin "1") (pinfunction "1_1") (pintype "passive"))
      (node (ref "C35") (pin "2") (pinfunction "2_2") (pintype "passive"))
      (node (ref "C36") (pin "1") (pinfunction "1_1") (pintype "passive"))
      (node (ref "C37") (pin "2") (pinfunction "2_2") (pintype "passive"))
      (node (ref "C38") (pin "1") (pinfunction "1_1") (pintype "passive"))
      (node (ref "C39") (pin "2") (pinfunction "2_2") (pintype "passive"))
      (node (ref "C4") (pin "2") (pinfunction "2_2") (pintype "passive"))
      (node (ref "C40") (pin "2") (pinfunction "2_2") (pintype "passive"))
      (node (ref "C41") (pin "2") (pinfunction "2_2") (pintype "passive"))
      (node (ref "C42") (pin "2") (pinfunction "2_2") (pintype "passive"))
      (node (ref "C43") (pin "2") (pinfunction "2_2") (pintype "passive"))
      (node (ref "C44") (pin "2") (pinfunction "2_2") (pintype "passive"))
      (node (ref "C45") (pin "2") (pinfunction "2_2") (pintype "passive"))
      (node (ref "C46") (pin "2") (pinfunction "2_2") (pintype "passive"))
      (node (ref "C47") (pin "2") (pinfunction "2_2") (pintype "passive"))
      (node (ref "C48") (pin "2") (pinfunction "2_2") (pintype "passive"))
      (node (ref "C49") (pin "2") (pinfunction "2_2") (pintype "passive"))
      (node (ref "C5") (pin "2") (pinfunction "2_2") (pintype "passive"))
      (node (ref "C50") (pin "2") (pinfunction "2_2") (pintype "passive"))
      (node (ref "C51") (pin "2") (pinfunction "2_2") (pintype "passive"))
      (node (ref "C52") (pin "2") (pinfunction "2_2") (pintype "passive"))
      (node (ref "C53") (pin "2") (pinfunction "2_2") (pintype "passive"))
      (node (ref "C54") (pin "2") (pinfunction "2_2") (pintype "passive"))
      (node (ref "C55") (pin "2") (pinfunction "2_2") (pintype "passive"))
      (node (ref "C56") (pin "2") (pinfunction "2_2") (pintype "passive"))
      (node (ref "C57") (pin "2") (pinfunction "2_2") (pintype "passive"))
      (node (ref "C58") (pin "2") (pinfunction "2_2") (pintype "passive"))
      (node (ref "C59") (pin "2") (pinfunction "2_2") (pintype "passive"))
      (node (ref "C6") (pin "2") (pinfunction "2_2") (pintype "passive"))
      (node (ref "C60") (pin "2") (pinfunction "2_2") (pintype "passive"))
      (node (ref "C61") (pin "2") (pinfunction "2_2") (pintype "passive"))
      (node (ref "C62") (pin "1") (pinfunction "1_1") (pintype "passive"))
      (node (ref "C63") (pin "1") (pinfunction "1_1") (pintype "passive"))
      (node (ref "C64") (pin "2") (pinfunction "2_2") (pintype "passive"))
      (node (ref "C65") (pin "2") (pinfunction "2_2") (pintype "passive"))
      (node (ref "C66") (pin "2") (pinfunction "2_2") (pintype "passive"))
      (node (ref "C7") (pin "2") (pinfunction "2_2") (pintype "passive"))
      (node (ref "C8") (pin "2") (pinfunction "2_2") (pintype "passive"))
      (node (ref "C9") (pin "2") (pinfunction "2_2") (pintype "passive"))
      (node (ref "H1") (pin "B3,2") (pinfunction "MOUNT_B3,2") (pintype "passive"))
      (node (ref "H2") (pin "B3,2") (pinfunction "MOUNT_B3,2") (pintype "passive"))
      (node (ref "JP1") (pin "4") (pinfunction "GND_4") (pintype "power_in"))
      (node (ref "JP1") (pin "5") (pinfunction "GND_5") (pintype "power_in"))
      (node (ref "JP1") (pin "GND1") (pinfunction "GND_GND1") (pintype "power_in"))
      (node (ref "JP1") (pin "GND2") (pinfunction "GND_GND2") (pintype "power_in"))
      (node (ref "JP4") (pin "1") (pinfunction "1_1") (pintype "bidirectional"))
      (node (ref "JP4") (pin "GND1") (pinfunction "GND_GND1") (pintype "power_in"))
      (node (ref "JP4") (pin "GND2") (pinfunction "GND_GND2") (pintype "power_in"))
      (node (ref "JP6") (pin "7") (pinfunction "7_7") (pintype "passive"))
      (node (ref "OSC1") (pin "2") (pinfunction "GND_2") (pintype "power_in"))
      (node (ref "Q1") (pin "2") (pinfunction "S_2") (pintype "output"))
      (node (ref "Q3") (pin "1") (pinfunction "S_1") (pintype "bidirectional"))
      (node (ref "Q3") (pin "3") (pinfunction "S_3") (pintype "bidirectional"))
      (node (ref "Q4") (pin "1") (pinfunction "S_1") (pintype "bidirectional"))
      (node (ref "Q4") (pin "2") (pinfunction "S_2") (pintype "bidirectional"))
      (node (ref "Q4") (pin "3") (pinfunction "S_3") (pintype "bidirectional"))
      (node (ref "R1") (pin "2") (pinfunction "2_2") (pintype "passive"))
      (node (ref "R19") (pin "2") (pinfunction "2_2") (pintype "passive"))
      (node (ref "R20") (pin "1") (pinfunction "1_1") (pintype "passive"))
      (node (ref "R22") (pin "2") (pinfunction "2_2") (pintype "passive"))
      (node (ref "R24") (pin "1") (pinfunction "1_1") (pintype "passive"))
      (node (ref "R26") (pin "2") (pinfunction "2_2") (pintype "passive"))
      (node (ref "R28") (pin "1") (pinfunction "1_1") (pintype "passive"))
      (node (ref "U1") (pin "108") (pinfunction "GND_108") (pintype "power_in"))
      (node (ref "U1") (pin "113") (pinfunction "GND_113") (pintype "power_in"))
      (node (ref "U1") (pin "13") (pinfunction "GND_13") (pintype "power_in"))
      (node (ref "U1") (pin "130") (pinfunction "GND_130") (pintype "power_in"))
      (node (ref "U1") (pin "136") (pinfunction "GND_136") (pintype "power_in"))
      (node (ref "U1") (pin "144") (pinfunction "L1_HSWAPEN_144") (pintype "bidirectional"))
      (node (ref "U1") (pin "25") (pinfunction "GND_25") (pintype "power_in"))
      (node (ref "U1") (pin "3") (pinfunction "GND_3") (pintype "power_in"))
      (node (ref "U1") (pin "49") (pinfunction "GND_49") (pintype "power_in"))
      (node (ref "U1") (pin "54") (pinfunction "GND_54") (pintype "power_in"))
      (node (ref "U1") (pin "68") (pinfunction "GND_68") (pintype "power_in"))
      (node (ref "U1") (pin "73") (pinfunction "SUSPEND_73") (pintype "input"))
      (node (ref "U1") (pin "77") (pinfunction "GND_77") (pintype "power_in"))
      (node (ref "U1") (pin "91") (pinfunction "GND_91") (pintype "power_in"))
      (node (ref "U1") (pin "96") (pinfunction "GND_96") (pintype "power_in"))
      (node (ref "U2") (pin "15") (pinfunction "AGND_15") (pintype "power_in"))
      (node (ref "U2") (pin "19") (pinfunction "AGND_19") (pintype "power_in"))
      (node (ref "U2") (pin "35") (pinfunction "IOGND_35") (pintype "power_in"))
      (node (ref "U2") (pin "36") (pinfunction "DGND_36") (pintype "power_in"))
      (node (ref "U2") (pin "47") (pinfunction "IOGND_47") (pintype "power_in"))
      (node (ref "U3") (pin "11") (pinfunction "PGND4_11") (pintype "power_in"))
      (node (ref "U3") (pin "13") (pinfunction "GND_1_13") (pintype "power_in"))
      (node (ref "U3") (pin "17") (pinfunction "GND_2_17") (pintype "power_in"))
      (node (ref "U3") (pin "18") (pinfunction "GND_3_18") (pintype "power_in"))
      (node (ref "U3") (pin "19") (pinfunction "GND_4_19") (pintype "power_in"))
      (node (ref "U3") (pin "2") (pinfunction "PGND3_2") (pintype "power_in"))
      (node (ref "U3") (pin "30") (pinfunction "PGND_30") (pintype "power_in"))
      (node (ref "U3") (pin "43") (pinfunction "SYNC/MODE_43") (pintype "bidirectional"))
      (node (ref "U3") (pin "5") (pinfunction "EN5_5") (pintype "input"))
      (node (ref "U3") (pin "PAD") (pinfunction "PGND_PAD") (pintype "power_in"))
      (node (ref "U4") (pin "4") (pinfunction "GND_4") (pintype "power_in"))
      (node (ref "U5") (pin "7") (pinfunction "GND_7") (pintype "power_in"))
      (node (ref "Y1") (pin "2") (pinfunction "GND_2") (pintype "power_in"))
      (node (ref "Y1") (pin "4") (pinfunction "GND_4") (pintype "power_in"))
    )
    (net (code "23") (name "MISO") (class "Default")
      (node (ref "JP6") (pin "4") (pinfunction "4_4") (pintype "passive"))
      (node (ref "U1") (pin "65") (pinfunction "L3_D0_DIN-MISO_MISO1_65") (pintype "bidirectional"))
      (node (ref "U4") (pin "2") (pinfunction "DOUT_2") (pintype "output"))
    )
    (net (code "24") (name "MOSI") (class "Default")
      (node (ref "JP6") (pin "5") (pinfunction "5_5") (pintype "passive"))
      (node (ref "U1") (pin "64") (pinfunction "~{L3}_MOSI_CSI_B_MISO0_64") (pintype "bidirectional"))
      (node (ref "U4") (pin "5") (pinfunction "DIN_5") (pintype "input"))
    )
    (net (code "25") (name "Net-(C26-Pad2)") (class "Default")
      (node (ref "C26") (pin "2") (pinfunction "2_2") (pintype "passive"))
      (node (ref "R15") (pin "2") (pinfunction "2_2") (pintype "passive"))
    )
    (net (code "26") (name "Net-(C27-Pad1)") (class "Default")
      (node (ref "C27") (pin "1") (pinfunction "1_1") (pintype "passive"))
      (node (ref "R16") (pin "1") (pinfunction "1_1") (pintype "passive"))
    )
    (net (code "27") (name "Net-(C28-Pad2)") (class "Default")
      (node (ref "C28") (pin "2") (pinfunction "2_2") (pintype "passive"))
      (node (ref "R17") (pin "2") (pinfunction "2_2") (pintype "passive"))
    )
    (net (code "28") (name "Net-(C29-Pad1)") (class "Default")
      (node (ref "C29") (pin "1") (pinfunction "1_1") (pintype "passive"))
      (node (ref "R18") (pin "2") (pinfunction "2_2") (pintype "passive"))
    )
    (net (code "29") (name "Net-(JP1B-A)") (class "Default")
      (node (ref "JP1") (pin "12") (pinfunction "A_12") (pintype "passive"))
      (node (ref "R9") (pin "2") (pinfunction "2_2") (pintype "passive"))
    )
    (net (code "30") (name "Net-(JP1C-A)") (class "Default")
      (node (ref "JP1") (pin "10") (pinfunction "A_10") (pintype "passive"))
      (node (ref "R8") (pin "2") (pinfunction "2_2") (pintype "passive"))
    )
    (net (code "31") (name "Net-(JP3-Pad2)") (class "Default")
      (node (ref "JP3") (pin "2") (pinfunction "2_2") (pintype "passive"))
      (node (ref "JP3") (pin "3") (pinfunction "3_3") (pintype "passive"))
      (node (ref "Q4") (pin "5") (pinfunction "D_5") (pintype "bidirectional"))
      (node (ref "Q4") (pin "6") (pinfunction "D_6") (pintype "bidirectional"))
      (node (ref "Q4") (pin "7") (pinfunction "D_7") (pintype "bidirectional"))
      (node (ref "Q4") (pin "8") (pinfunction "D_8") (pintype "bidirectional"))
    )
    (net (code "32") (name "Net-(OSC1-OUT)") (class "Default")
      (node (ref "OSC1") (pin "3") (pinfunction "OUT_3") (pintype "output"))
      (node (ref "U1") (pin "123") (pinfunction "~{L37}_GCLK12_123") (pintype "bidirectional"))
    )
    (net (code "33") (name "Net-(Q1-D)") (class "Default")
      (node (ref "Q1") (pin "3") (pinfunction "D_3") (pintype "input"))
      (node (ref "Q2") (pin "3") (pinfunction "D_3") (pintype "bidirectional"))
      (node (ref "SPEED") (pin "2") (pinfunction "P$2_2") (pintype "passive"))
    )
    (net (code "34") (name "Net-(Q1-G)") (class "Default")
      (node (ref "Q1") (pin "1") (pinfunction "G_1") (pintype "input"))
      (node (ref "Q2") (pin "1") (pinfunction "G_1") (pintype "input"))
      (node (ref "R10") (pin "1") (pinfunction "1_1") (pintype "passive"))
    )
    (net (code "35") (name "Net-(Q3A-G)") (class "Default")
      (node (ref "Q3") (pin "4") (pinfunction "G_4") (pintype "input"))
      (node (ref "U3") (pin "31") (pinfunction "DL1_31") (pintype "output"))
    )
    (net (code "36") (name "Net-(Q3B-G)") (class "Default")
      (node (ref "Q3") (pin "2") (pinfunction "G_2") (pintype "input"))
      (node (ref "U3") (pin "29") (pinfunction "DL2_29") (pintype "output"))
    )
    (net (code "37") (name "Net-(Q4-G)") (class "Default")
      (node (ref "Q4") (pin "4") (pinfunction "G_4") (pintype "input"))
      (node (ref "R34") (pin "2") (pinfunction "2_2") (pintype "passive"))
    )
    (net (code "38") (name "Net-(SPEED-P$1)") (class "Default")
      (node (ref "R7") (pin "1") (pinfunction "1_1") (pintype "passive"))
      (node (ref "SPEED") (pin "1") (pinfunction "P$1_1") (pintype "passive"))
    )
    (net (code "39") (name "Net-(U1B-L1)") (class "Default")
      (node (ref "R36") (pin "2") (pinfunction "2_2") (pintype "passive"))
      (node (ref "U1") (pin "105") (pinfunction "L1_105") (pintype "bidirectional"))
      (node (ref "U2") (pin "30") (pinfunction "MDIO_30") (pintype "bidirectional"))
    )
    (net (code "40") (name "Net-(U1B-L40_GCLK11)") (class "Default")
      (node (ref "U1") (pin "95") (pinfunction "L40_GCLK11_95") (pintype "bidirectional"))
      (node (ref "U2") (pin "31") (pinfunction "MDC_31") (pintype "input"))
    )
    (net (code "41") (name "Net-(U1B-L41_GCLK9_IRDY1)") (class "Default")
      (node (ref "U1") (pin "93") (pinfunction "L41_GCLK9_IRDY1_93") (pintype "bidirectional"))
      (node (ref "U2") (pin "40") (pinfunction "CRS/CRS_DV/LED_CFG_40") (pintype "output"))
    )
    (net (code "42") (name "Net-(U1B-L42_GCLK7)") (class "Default")
      (node (ref "U1") (pin "88") (pinfunction "L42_GCLK7_88") (pintype "bidirectional"))
      (node (ref "U2") (pin "39") (pinfunction "RX_DV/MII_MODE_39") (pintype "output"))
    )
    (net (code "43") (name "Net-(U1B-L43_GCLK5)") (class "Default")
      (node (ref "U1") (pin "85") (pinfunction "L43_GCLK5_85") (pintype "bidirectional"))
      (node (ref "U2") (pin "1") (pinfunction "TX_CLK_1") (pintype "output"))
    )
    (net (code "44") (name "Net-(U1B-~{L34})") (class "Default")
      (node (ref "U1") (pin "97") (pinfunction "~{L34}_97") (pintype "bidirectional"))
      (node (ref "U2") (pin "42") (pinfunction "COL/PHYAD0_42") (pintype "output"))
    )
    (net (code "45") (name "Net-(U1B-~{L40}_GCLK10)") (class "Default")
      (node (ref "U1") (pin "94") (pinfunction "~{L40}_GCLK10_94") (pintype "bidirectional"))
      (node (ref "U2") (pin "25") (pinfunction "CLK_OUT_25") (pintype "output"))
    )
    (net (code "46") (name "Net-(U1B-~{L41}_GCLK8)") (class "Default")
      (node (ref "U1") (pin "92") (pinfunction "~{L41}_GCLK8_92") (pintype "bidirectional"))
      (node (ref "U2") (pin "38") (pinfunction "RX_CLK_38") (pintype "output"))
    )
    (net (code "47") (name "Net-(U1B-~{L42}_GCLK6_TRDY1)") (class "Default")
      (node (ref "U1") (pin "87") (pinfunction "~{L42}_GCLK6_TRDY1_87") (pintype "bidirectional"))
      (node (ref "U2") (pin "41") (pinfunction "RX_ER/AMDIX_EN_41") (pintype "output"))
    )
    (net (code "48") (name "Net-(U1B-~{L43}_GCLK4)") (class "Default")
      (node (ref "U1") (pin "84") (pinfunction "~{L43}_GCLK4_84") (pintype "bidirectional"))
      (node (ref "U2") (pin "2") (pinfunction "TX_EN_2") (pintype "input"))
    )
    (net (code "49") (name "Net-(U1C-L13_M1)") (class "Default")
      (node (ref "R28") (pin "2") (pinfunction "2_2") (pintype "passive"))
      (node (ref "U1") (pin "60") (pinfunction "L13_M1_60") (pintype "bidirectional"))
    )
    (net (code "50") (name "Net-(U1C-L65_INIT_B)") (class "Default")
      (node (ref "R31") (pin "1") (pinfunction "1_1") (pintype "passive"))
      (node (ref "U1") (pin "39") (pinfunction "L65_INIT_B_39") (pintype "bidirectional"))
    )
    (net (code "51") (name "Net-(U1C-~{L1}_M0_CMPMISO)") (class "Default")
      (node (ref "R29") (pin "2") (pinfunction "2_2") (pintype "passive"))
      (node (ref "U1") (pin "69") (pinfunction "~{L1}_M0_CMPMISO_69") (pintype "bidirectional"))
    )
    (net (code "52") (name "Net-(U1D-L44_GCLK21)") (class "Default")
      (node (ref "U1") (pin "15") (pinfunction "L44_GCLK21_15") (pintype "bidirectional"))
      (node (ref "U5") (pin "3") (pinfunction "A2_3") (pintype "bidirectional"))
    )
    (net (code "53") (name "Net-(U1D-~{L43}_GCLK22_IRDY2)") (class "Default")
      (node (ref "U1") (pin "16") (pinfunction "~{L43}_GCLK22_IRDY2_16") (pintype "bidirectional"))
      (node (ref "U5") (pin "2") (pinfunction "A1_2") (pintype "bidirectional"))
    )
    (net (code "54") (name "Net-(U1D-~{L44}_GCLK20)") (class "Default")
      (node (ref "U1") (pin "14") (pinfunction "~{L44}_GCLK20_14") (pintype "bidirectional"))
      (node (ref "U5") (pin "4") (pinfunction "A3_4") (pintype "bidirectional"))
    )
    (net (code "55") (name "Net-(U2-RBIAS)") (class "Default")
      (node (ref "R1") (pin "1") (pinfunction "1_1") (pintype "passive"))
      (node (ref "U2") (pin "24") (pinfunction "RBIAS_24") (pintype "input"))
    )
    (net (code "56") (name "Net-(U2-RESERVED)") (class "Default")
      (node (ref "R2") (pin "1") (pinfunction "1_1") (pintype "passive"))
      (node (ref "U2") (pin "20") (pinfunction "RESERVED_20") (pintype "bidirectional"))
    )
    (net (code "57") (name "Net-(U2-XI)") (class "Default")
      (node (ref "C62") (pin "2") (pinfunction "2_2") (pintype "passive"))
      (node (ref "U2") (pin "34") (pinfunction "XI_34") (pintype "passive"))
      (node (ref "Y1") (pin "1") (pinfunction "1_1") (pintype "passive"))
    )
    (net (code "58") (name "Net-(U2-XO)") (class "Default")
      (node (ref "C63") (pin "2") (pinfunction "2_2") (pintype "passive"))
      (node (ref "U2") (pin "33") (pinfunction "XO_33") (pintype "passive"))
      (node (ref "Y1") (pin "3") (pinfunction "2_3") (pintype "passive"))
    )
    (net (code "59") (name "Net-(U2-~{RESET})") (class "Default")
      (node (ref "R14") (pin "2") (pinfunction "2_2") (pintype "passive"))
      (node (ref "U2") (pin "29") (pinfunction "~{RESET}_29") (pintype "input"))
    )
    (net (code "60") (name "Net-(U2-~{SW_STRAP})") (class "Default")
      (node (ref "R35") (pin "1") (pinfunction "1_1") (pintype "passive"))
      (node (ref "U2") (pin "21") (pinfunction "~{SW_STRAP}_21") (pintype "input"))
    )
    (net (code "61") (name "Net-(U3-BST1)") (class "Default")
      (node (ref "C25") (pin "1") (pinfunction "1_1") (pintype "passive"))
      (node (ref "U3") (pin "32") (pinfunction "BST1_32") (pintype "passive"))
    )
    (net (code "62") (name "Net-(U3-BST2)") (class "Default")
      (node (ref "C32") (pin "1") (pinfunction "1_1") (pintype "passive"))
      (node (ref "U3") (pin "28") (pinfunction "BST2_28") (pintype "passive"))
    )
    (net (code "63") (name "Net-(U3-BST3)") (class "Default")
      (node (ref "C34") (pin "1") (pinfunction "1_1") (pintype "passive"))
      (node (ref "U3") (pin "1") (pinfunction "BST3_1") (pintype "passive"))
    )
    (net (code "64") (name "Net-(U3-BST4)") (class "Default")
      (node (ref "C33") (pin "1") (pinfunction "1_1") (pintype "passive"))
      (node (ref "U3") (pin "12") (pinfunction "BST4_12") (pintype "passive"))
    )
    (net (code "65") (name "Net-(U3-COMP1)") (class "Default")
      (node (ref "R15") (pin "1") (pinfunction "1_1") (pintype "passive"))
      (node (ref "U3") (pin "39") (pinfunction "COMP1_39") (pintype "passive"))
    )
    (net (code "66") (name "Net-(U3-COMP2)") (class "Default")
      (node (ref "R16") (pin "2") (pinfunction "2_2") (pintype "passive"))
      (node (ref "U3") (pin "22") (pinfunction "COMP2_22") (pintype "passive"))
    )
    (net (code "67") (name "Net-(U3-COMP3)") (class "Default")
      (node (ref "R17") (pin "1") (pinfunction "1_1") (pintype "passive"))
      (node (ref "U3") (pin "46") (pinfunction "COMP3_46") (pintype "passive"))
    )
    (net (code "68") (name "Net-(U3-COMP4)") (class "Default")
      (node (ref "R18") (pin "1") (pinfunction "1_1") (pintype "passive"))
      (node (ref "U3") (pin "15") (pinfunction "COMP4_15") (pintype "passive"))
    )
    (net (code "69") (name "Net-(U3-FB1)") (class "Default")
      (node (ref "R20") (pin "2") (pinfunction "2_2") (pintype "passive"))
      (node (ref "R21") (pin "2") (pinfunction "2_2") (pintype "passive"))
      (node (ref "U3") (pin "40") (pinfunction "FB1_40") (pintype "input"))
    )
    (net (code "70") (name "Net-(U3-FB2)") (class "Default")
      (node (ref "R22") (pin "1") (pinfunction "1_1") (pintype "passive"))
      (node (ref "R23") (pin "1") (pinfunction "1_1") (pintype "passive"))
      (node (ref "U3") (pin "21") (pinfunction "FB2_21") (pintype "input"))
    )
    (net (code "71") (name "Net-(U3-FB3)") (class "Default")
      (node (ref "R24") (pin "2") (pinfunction "2_2") (pintype "passive"))
      (node (ref "R25") (pin "2") (pinfunction "2_2") (pintype "passive"))
      (node (ref "U3") (pin "45") (pinfunction "FB3_45") (pintype "input"))
    )
    (net (code "72") (name "Net-(U3-FB4)") (class "Default")
      (node (ref "R26") (pin "1") (pinfunction "1_1") (pintype "passive"))
      (node (ref "R27") (pin "1") (pinfunction "1_1") (pintype "passive"))
      (node (ref "U3") (pin "16") (pinfunction "FB4_16") (pintype "input"))
    )
    (net (code "73") (name "Net-(U3-RT)") (class "Default")
      (node (ref "R19") (pin "1") (pinfunction "1_1") (pintype "passive"))
      (node (ref "U3") (pin "41") (pinfunction "RT_41") (pintype "passive"))
    )
    (net (code "74") (name "Net-(U3-SS12)") (class "Default")
      (node (ref "C30") (pin "2") (pinfunction "2_2") (pintype "passive"))
      (node (ref "U3") (pin "38") (pinfunction "SS12_38") (pintype "passive"))
      (node (ref "U3") (pin "44") (pinfunction "VREG_44") (pintype "output"))
      (node (ref "U3") (pin "47") (pinfunction "SS34_47") (pintype "passive"))
    )
    (net (code "75") (name "Net-(U3-SW1_1)") (class "Default")
      (node (ref "C25") (pin "2") (pinfunction "2_2") (pintype "passive"))
      (node (ref "L1") (pin "1") (pinfunction "1_1") (pintype "passive"))
      (node (ref "Q3") (pin "5") (pinfunction "D_5") (pintype "bidirectional"))
      (node (ref "Q3") (pin "6") (pinfunction "D_6") (pintype "bidirectional"))
      (node (ref "U3") (pin "33") (pinfunction "SW1_1_33") (pintype "output"))
      (node (ref "U3") (pin "34") (pinfunction "SW1_2_34") (pintype "output"))
    )
    (net (code "76") (name "Net-(U3-SW2_1)") (class "Default")
      (node (ref "C32") (pin "2") (pinfunction "2_2") (pintype "passive"))
      (node (ref "L2") (pin "1") (pinfunction "1_1") (pintype "passive"))
      (node (ref "Q3") (pin "7") (pinfunction "D_7") (pintype "bidirectional"))
      (node (ref "Q3") (pin "8") (pinfunction "D_8") (pintype "bidirectional"))
      (node (ref "U3") (pin "26") (pinfunction "SW2_1_26") (pintype "output"))
      (node (ref "U3") (pin "27") (pinfunction "SW2_2_27") (pintype "output"))
    )
    (net (code "77") (name "Net-(U3-SW3)") (class "Default")
      (node (ref "C34") (pin "2") (pinfunction "2_2") (pintype "passive"))
      (node (ref "L3") (pin "2") (pinfunction "2_2") (pintype "passive"))
      (node (ref "U3") (pin "3") (pinfunction "SW3_3") (pintype "output"))
    )
    (net (code "78") (name "Net-(U3-SW4)") (class "Default")
      (node (ref "C33") (pin "2") (pinfunction "2_2") (pintype "passive"))
      (node (ref "L4") (pin "2") (pinfunction "2_2") (pintype "passive"))
      (node (ref "U3") (pin "10") (pinfunction "SW4_10") (pintype "output"))
    )
    (net (code "79") (name "Net-(U3-VDD)") (class "Default")
      (node (ref "C31") (pin "2") (pinfunction "2_2") (pintype "passive"))
      (node (ref "U3") (pin "42") (pinfunction "VDD_42") (pintype "power_in"))
    )
    (net (code "80") (name "Net-(U5-B1)") (class "Default")
      (node (ref "JP4") (pin "4") (pinfunction "4_4") (pintype "bidirectional"))
      (node (ref "U5") (pin "13") (pinfunction "B1_13") (pintype "bidirectional"))
    )
    (net (code "81") (name "Net-(U5-B2)") (class "Default")
      (node (ref "JP4") (pin "3") (pinfunction "3_3") (pintype "bidirectional"))
      (node (ref "U5") (pin "12") (pinfunction "B2_12") (pintype "bidirectional"))
    )
    (net (code "82") (name "Net-(U5-B3)") (class "Default")
      (node (ref "JP4") (pin "2") (pinfunction "2_2") (pintype "bidirectional"))
      (node (ref "U5") (pin "11") (pinfunction "B3_11") (pintype "bidirectional"))
    )
    (net (code "83") (name "RX+") (class "Default")
      (node (ref "JP1") (pin "7") (pinfunction "RX+_7") (pintype "passive"))
      (node (ref "R3") (pin "2") (pinfunction "2_2") (pintype "passive"))
      (node (ref "U2") (pin "14") (pinfunction "RD_14") (pintype "bidirectional"))
    )
    (net (code "84") (name "RX-") (class "Default")
      (node (ref "JP1") (pin "8") (pinfunction "RX-_8") (pintype "passive"))
      (node (ref "R4") (pin "1") (pinfunction "1_1") (pintype "passive"))
      (node (ref "U2") (pin "13") (pinfunction "~{RD}_13") (pintype "bidirectional"))
    )
    (net (code "85") (name "SPI_CLK") (class "Default")
      (node (ref "JP6") (pin "6") (pinfunction "6_6") (pintype "passive"))
      (node (ref "U1") (pin "70") (pinfunction "L1_CCLK_70") (pintype "bidirectional"))
      (node (ref "U4") (pin "6") (pinfunction "CLK_6") (pintype "input"))
    )
    (net (code "86") (name "TX+") (class "Default")
      (node (ref "JP1") (pin "1") (pinfunction "TX+_1") (pintype "passive"))
      (node (ref "R5") (pin "2") (pinfunction "2_2") (pintype "passive"))
      (node (ref "U2") (pin "17") (pinfunction "TD_17") (pintype "bidirectional"))
    )
    (net (code "87") (name "TX-") (class "Default")
      (node (ref "JP1") (pin "2") (pinfunction "TX-_2") (pintype "passive"))
      (node (ref "R6") (pin "1") (pinfunction "1_1") (pintype "passive"))
      (node (ref "U2") (pin "16") (pinfunction "~{TD}_16") (pintype "bidirectional"))
    )
    (net (code "88") (name "unconnected-(JP6-Pad2)") (class "Default")
      (node (ref "JP6") (pin "2") (pinfunction "2_2") (pintype "passive"))
    )
    (net (code "89") (name "unconnected-(U1A-L2-Pad142)") (class "Default")
      (node (ref "U1") (pin "142") (pinfunction "L2_142") (pintype "bidirectional"))
    )
    (net (code "90") (name "unconnected-(U1A-L3-Pad140)") (class "Default")
      (node (ref "U1") (pin "140") (pinfunction "L3_140") (pintype "bidirectional"))
    )
    (net (code "91") (name "unconnected-(U1A-L4-Pad138)") (class "Default")
      (node (ref "U1") (pin "138") (pinfunction "L4_138") (pintype "bidirectional"))
    )
    (net (code "92") (name "unconnected-(U1A-L34_GCLK19-Pad134)") (class "Default")
      (node (ref "U1") (pin "134") (pinfunction "L34_GCLK19_134") (pintype "bidirectional"))
    )
    (net (code "93") (name "unconnected-(U1A-L35_GCLK17-Pad132)") (class "Default")
      (node (ref "U1") (pin "132") (pinfunction "L35_GCLK17_132") (pintype "bidirectional"))
    )
    (net (code "94") (name "unconnected-(U1A-L36_GCLK15-Pad127)") (class "Default")
      (node (ref "U1") (pin "127") (pinfunction "L36_GCLK15_127") (pintype "bidirectional"))
    )
    (net (code "95") (name "unconnected-(U1A-L37_GCLK13-Pad124)") (class "Default")
      (node (ref "U1") (pin "124") (pinfunction "L37_GCLK13_124") (pintype "bidirectional"))
    )
    (net (code "96") (name "unconnected-(U1A-L62-Pad121)") (class "Default")
      (node (ref "U1") (pin "121") (pinfunction "L62_121") (pintype "bidirectional"))
    )
    (net (code "97") (name "unconnected-(U1A-L63_SCP7-Pad119)") (class "Default")
      (node (ref "U1") (pin "119") (pinfunction "L63_SCP7_119") (pintype "bidirectional"))
    )
    (net (code "98") (name "unconnected-(U1A-L64_SCP5-Pad117)") (class "Default")
      (node (ref "U1") (pin "117") (pinfunction "L64_SCP5_117") (pintype "bidirectional"))
    )
    (net (code "99") (name "unconnected-(U1A-L65_SCP3-Pad115)") (class "Default")
      (node (ref "U1") (pin "115") (pinfunction "L65_SCP3_115") (pintype "bidirectional"))
    )
    (net (code "100") (name "unconnected-(U1A-L66_SCP1-Pad112)") (class "Default")
      (node (ref "U1") (pin "112") (pinfunction "L66_SCP1_112") (pintype "bidirectional"))
    )
    (net (code "101") (name "unconnected-(U1A-~{L1}_VREF-Pad143)") (class "Default")
      (node (ref "U1") (pin "143") (pinfunction "~{L1}_VREF_143") (pintype "bidirectional"))
    )
    (net (code "102") (name "unconnected-(U1A-~{L2}-Pad141)") (class "Default")
      (node (ref "U1") (pin "141") (pinfunction "~{L2}_141") (pintype "bidirectional"))
    )
    (net (code "103") (name "unconnected-(U1A-~{L3}-Pad139)") (class "Default")
      (node (ref "U1") (pin "139") (pinfunction "~{L3}_139") (pintype "bidirectional"))
    )
    (net (code "104") (name "unconnected-(U1A-~{L4}-Pad137)") (class "Default")
      (node (ref "U1") (pin "137") (pinfunction "~{L4}_137") (pintype "bidirectional"))
    )
    (net (code "105") (name "unconnected-(U1A-~{L34}_GCLK18-Pad133)") (class "Default")
      (node (ref "U1") (pin "133") (pinfunction "~{L34}_GCLK18_133") (pintype "bidirectional"))
    )
    (net (code "106") (name "unconnected-(U1A-~{L35}_GCLK16-Pad131)") (class "Default")
      (node (ref "U1") (pin "131") (pinfunction "~{L35}_GCLK16_131") (pintype "bidirectional"))
    )
    (net (code "107") (name "unconnected-(U1A-~{L36}_GCLK14-Pad126)") (class "Default")
      (node (ref "U1") (pin "126") (pinfunction "~{L36}_GCLK14_126") (pintype "bidirectional"))
    )
    (net (code "108") (name "unconnected-(U1A-~{L62}_VREF-Pad120)") (class "Default")
      (node (ref "U1") (pin "120") (pinfunction "~{L62}_VREF_120") (pintype "bidirectional"))
    )
    (net (code "109") (name "unconnected-(U1A-~{L63}_SCP6-Pad118)") (class "Default")
      (node (ref "U1") (pin "118") (pinfunction "~{L63}_SCP6_118") (pintype "bidirectional"))
    )
    (net (code "110") (name "unconnected-(U1A-~{L64}_SCP4-Pad116)") (class "Default")
      (node (ref "U1") (pin "116") (pinfunction "~{L64}_SCP4_116") (pintype "bidirectional"))
    )
    (net (code "111") (name "unconnected-(U1A-~{L65}_SCP2-Pad114)") (class "Default")
      (node (ref "U1") (pin "114") (pinfunction "~{L65}_SCP2_114") (pintype "bidirectional"))
    )
    (net (code "112") (name "unconnected-(U1A-~{L66}_SCP0-Pad111)") (class "Default")
      (node (ref "U1") (pin "111") (pinfunction "~{L66}_SCP0_111") (pintype "bidirectional"))
    )
    (net (code "113") (name "unconnected-(U1B-L34-Pad98)") (class "Default")
      (node (ref "U1") (pin "98") (pinfunction "L34_98") (pintype "bidirectional"))
    )
    (net (code "114") (name "unconnected-(U1B-L47-Pad79)") (class "Default")
      (node (ref "U1") (pin "79") (pinfunction "L47_79") (pintype "bidirectional"))
    )
    (net (code "115") (name "unconnected-(U1B-L74_AWAKE-Pad75)") (class "Default")
      (node (ref "U1") (pin "75") (pinfunction "L74_AWAKE_75") (pintype "bidirectional"))
    )
    (net (code "116") (name "unconnected-(U1B-~{L1}_VREF-Pad104)") (class "Default")
      (node (ref "U1") (pin "104") (pinfunction "~{L1}_VREF_104") (pintype "bidirectional"))
    )
    (net (code "117") (name "unconnected-(U1B-~{L47}-Pad78)") (class "Default")
      (node (ref "U1") (pin "78") (pinfunction "~{L47}_78") (pintype "bidirectional"))
    )
    (net (code "118") (name "unconnected-(U1B-~{L74}_DOUT_BUSY-Pad74)") (class "Default")
      (node (ref "U1") (pin "74") (pinfunction "~{L74}_DOUT_BUSY_74") (pintype "bidirectional"))
    )
    (net (code "119") (name "unconnected-(U1C-L2_CMPCLK-Pad67)") (class "Default")
      (node (ref "U1") (pin "67") (pinfunction "L2_CMPCLK_67") (pintype "bidirectional"))
    )
    (net (code "120") (name "unconnected-(U1C-L12_D1_MISO2-Pad62)") (class "Default")
      (node (ref "U1") (pin "62") (pinfunction "L12_D1_MISO2_62") (pintype "bidirectional"))
    )
    (net (code "121") (name "unconnected-(U1C-L14_D11-Pad58)") (class "Default")
      (node (ref "U1") (pin "58") (pinfunction "L14_D11_58") (pintype "bidirectional"))
    )
    (net (code "122") (name "unconnected-(U1C-L30_GCLK1_D13-Pad56)") (class "Default")
      (node (ref "U1") (pin "56") (pinfunction "L30_GCLK1_D13_56") (pintype "bidirectional"))
    )
    (net (code "123") (name "unconnected-(U1C-L31_GCLK31_D14-Pad51)") (class "Default")
      (node (ref "U1") (pin "51") (pinfunction "L31_GCLK31_D14_51") (pintype "bidirectional"))
    )
    (net (code "124") (name "unconnected-(U1C-L48_D7-Pad48)") (class "Default")
      (node (ref "U1") (pin "48") (pinfunction "L48_D7_48") (pintype "bidirectional"))
    )
    (net (code "125") (name "unconnected-(U1C-L49_D3-Pad46)") (class "Default")
      (node (ref "U1") (pin "46") (pinfunction "L49_D3_46") (pintype "bidirectional"))
    )
    (net (code "126") (name "unconnected-(U1C-L62_D5-Pad44)") (class "Default")
      (node (ref "U1") (pin "44") (pinfunction "L62_D5_44") (pintype "bidirectional"))
    )
    (net (code "127") (name "unconnected-(U1C-L64_D8-Pad41)") (class "Default")
      (node (ref "U1") (pin "41") (pinfunction "L64_D8_41") (pintype "bidirectional"))
    )
    (net (code "128") (name "unconnected-(U1C-~{L2}_CMPMOSI-Pad66)") (class "Default")
      (node (ref "U1") (pin "66") (pinfunction "~{L2}_CMPMOSI_66") (pintype "bidirectional"))
    )
    (net (code "129") (name "unconnected-(U1C-~{L12}_D2_MISO3-Pad61)") (class "Default")
      (node (ref "U1") (pin "61") (pinfunction "~{L12}_D2_MISO3_61") (pintype "bidirectional"))
    )
    (net (code "130") (name "unconnected-(U1C-~{L13}_D10-Pad59)") (class "Default")
      (node (ref "U1") (pin "59") (pinfunction "~{L13}_D10_59") (pintype "bidirectional"))
    )
    (net (code "131") (name "unconnected-(U1C-~{L14}_D12-Pad57)") (class "Default")
      (node (ref "U1") (pin "57") (pinfunction "~{L14}_D12_57") (pintype "bidirectional"))
    )
    (net (code "132") (name "unconnected-(U1C-~{L30}_GCLK0_USERCCLK-Pad55)") (class "Default")
      (node (ref "U1") (pin "55") (pinfunction "~{L30}_GCLK0_USERCCLK_55") (pintype "bidirectional"))
    )
    (net (code "133") (name "unconnected-(U1C-~{L31}_GCLK30_D15-Pad50)") (class "Default")
      (node (ref "U1") (pin "50") (pinfunction "~{L31}_GCLK30_D15_50") (pintype "bidirectional"))
    )
    (net (code "134") (name "unconnected-(U1C-~{L48}_RDWR_B_VREF-Pad47)") (class "Default")
      (node (ref "U1") (pin "47") (pinfunction "~{L48}_RDWR_B_VREF_47") (pintype "bidirectional"))
    )
    (net (code "135") (name "unconnected-(U1C-~{L49}_D4-Pad45)") (class "Default")
      (node (ref "U1") (pin "45") (pinfunction "~{L49}_D4_45") (pintype "bidirectional"))
    )
    (net (code "136") (name "unconnected-(U1C-~{L62}_D6-Pad43)") (class "Default")
      (node (ref "U1") (pin "43") (pinfunction "~{L62}_D6_43") (pintype "bidirectional"))
    )
    (net (code "137") (name "unconnected-(U1C-~{L64}_D9-Pad40)") (class "Default")
      (node (ref "U1") (pin "40") (pinfunction "~{L64}_D9_40") (pintype "bidirectional"))
    )
    (net (code "138") (name "unconnected-(U1D-L1-Pad35)") (class "Default")
      (node (ref "U1") (pin "35") (pinfunction "L1_35") (pintype "bidirectional"))
    )
    (net (code "139") (name "unconnected-(U1D-L2-Pad33)") (class "Default")
      (node (ref "U1") (pin "33") (pinfunction "L2_33") (pintype "bidirectional"))
    )
    (net (code "140") (name "unconnected-(U1D-L36-Pad30)") (class "Default")
      (node (ref "U1") (pin "30") (pinfunction "L36_30") (pintype "bidirectional"))
    )
    (net (code "141") (name "unconnected-(U1D-L37-Pad27)") (class "Default")
      (node (ref "U1") (pin "27") (pinfunction "L37_27") (pintype "bidirectional"))
    )
    (net (code "142") (name "unconnected-(U1D-L41_GCLK27-Pad24)") (class "Default")
      (node (ref "U1") (pin "24") (pinfunction "L41_GCLK27_24") (pintype "bidirectional"))
    )
    (net (code "143") (name "unconnected-(U1D-L42_GCLK25_TRDY2-Pad22)") (class "Default")
      (node (ref "U1") (pin "22") (pinfunction "L42_GCLK25_TRDY2_22") (pintype "bidirectional"))
    )
    (net (code "144") (name "unconnected-(U1D-L43_GCLK23-Pad17)") (class "Default")
      (node (ref "U1") (pin "17") (pinfunction "L43_GCLK23_17") (pintype "bidirectional"))
    )
    (net (code "145") (name "unconnected-(U1D-L49-Pad12)") (class "Default")
      (node (ref "U1") (pin "12") (pinfunction "L49_12") (pintype "bidirectional"))
    )
    (net (code "146") (name "unconnected-(U1D-L50-Pad10)") (class "Default")
      (node (ref "U1") (pin "10") (pinfunction "L50_10") (pintype "bidirectional"))
    )
    (net (code "147") (name "unconnected-(U1D-L51-Pad8)") (class "Default")
      (node (ref "U1") (pin "8") (pinfunction "L51_8") (pintype "bidirectional"))
    )
    (net (code "148") (name "unconnected-(U1D-L52-Pad6)") (class "Default")
      (node (ref "U1") (pin "6") (pinfunction "L52_6") (pintype "bidirectional"))
    )
    (net (code "149") (name "unconnected-(U1D-L83-Pad2)") (class "Default")
      (node (ref "U1") (pin "2") (pinfunction "L83_2") (pintype "bidirectional"))
    )
    (net (code "150") (name "unconnected-(U1D-~{L1}_VREF-Pad34)") (class "Default")
      (node (ref "U1") (pin "34") (pinfunction "~{L1}_VREF_34") (pintype "bidirectional"))
    )
    (net (code "151") (name "unconnected-(U1D-~{L2}-Pad32)") (class "Default")
      (node (ref "U1") (pin "32") (pinfunction "~{L2}_32") (pintype "bidirectional"))
    )
    (net (code "152") (name "unconnected-(U1D-~{L36}-Pad29)") (class "Default")
      (node (ref "U1") (pin "29") (pinfunction "~{L36}_29") (pintype "bidirectional"))
    )
    (net (code "153") (name "unconnected-(U1D-~{L37}-Pad26)") (class "Default")
      (node (ref "U1") (pin "26") (pinfunction "~{L37}_26") (pintype "bidirectional"))
    )
    (net (code "154") (name "unconnected-(U1D-~{L41}_GCLK26-Pad23)") (class "Default")
      (node (ref "U1") (pin "23") (pinfunction "~{L41}_GCLK26_23") (pintype "bidirectional"))
    )
    (net (code "155") (name "unconnected-(U1D-~{L42}_GCLK24-Pad21)") (class "Default")
      (node (ref "U1") (pin "21") (pinfunction "~{L42}_GCLK24_21") (pintype "bidirectional"))
    )
    (net (code "156") (name "unconnected-(U1D-~{L49}-Pad11)") (class "Default")
      (node (ref "U1") (pin "11") (pinfunction "~{L49}_11") (pintype "bidirectional"))
    )
    (net (code "157") (name "unconnected-(U1D-~{L50}-Pad9)") (class "Default")
      (node (ref "U1") (pin "9") (pinfunction "~{L50}_9") (pintype "bidirectional"))
    )
    (net (code "158") (name "unconnected-(U1D-~{L51}-Pad7)") (class "Default")
      (node (ref "U1") (pin "7") (pinfunction "~{L51}_7") (pintype "bidirectional"))
    )
    (net (code "159") (name "unconnected-(U1D-~{L52}-Pad5)") (class "Default")
      (node (ref "U1") (pin "5") (pinfunction "~{L52}_5") (pintype "bidirectional"))
    )
    (net (code "160") (name "unconnected-(U1D-~{L83}_VREF-Pad1)") (class "Default")
      (node (ref "U1") (pin "1") (pinfunction "~{L83}_VREF_1") (pintype "bidirectional"))
    )
    (net (code "161") (name "unconnected-(U1E-CMPCS_B-Pad72)") (class "Default")
      (node (ref "U1") (pin "72") (pinfunction "CMPCS_B_72") (pintype "bidirectional"))
    )
    (net (code "162") (name "unconnected-(U1E-TCK-Pad109)") (class "Default")
      (node (ref "U1") (pin "109") (pinfunction "TCK_109") (pintype "input"))
    )
    (net (code "163") (name "unconnected-(U1E-TDI-Pad110)") (class "Default")
      (node (ref "U1") (pin "110") (pinfunction "TDI_110") (pintype "input"))
    )
    (net (code "164") (name "unconnected-(U1E-TDO-Pad106)") (class "Default")
      (node (ref "U1") (pin "106") (pinfunction "TDO_106") (pintype "output"))
    )
    (net (code "165") (name "unconnected-(U1E-TMS-Pad107)") (class "Default")
      (node (ref "U1") (pin "107") (pinfunction "TMS_107") (pintype "input"))
    )
    (net (code "166") (name "unconnected-(U2-JTAG_TCK-Pad8)") (class "Default")
      (node (ref "U2") (pin "8") (pinfunction "JTAG_TCK_8") (pintype "input"))
    )
    (net (code "167") (name "unconnected-(U2-JTAG_TDI-Pad12)") (class "Default")
      (node (ref "U2") (pin "12") (pinfunction "JTAG_TDI_12") (pintype "input"))
    )
    (net (code "168") (name "unconnected-(U2-JTAG_TDO-Pad9)") (class "Default")
      (node (ref "U2") (pin "9") (pinfunction "JTAG_TDO_9") (pintype "output"))
    )
    (net (code "169") (name "unconnected-(U2-JTAG_TMS-Pad10)") (class "Default")
      (node (ref "U2") (pin "10") (pinfunction "JTAG_TMS_10") (pintype "input"))
    )
    (net (code "170") (name "unconnected-(U2-~{INT{slash}PWDN}-Pad7)") (class "Default")
      (node (ref "U2") (pin "7") (pinfunction "~{INT/PWDN}_7") (pintype "bidirectional"))
    )
    (net (code "171") (name "unconnected-(U2-~{JTAG_TRST}-Pad11)") (class "Default")
      (node (ref "U2") (pin "11") (pinfunction "~{JTAG_TRST}_11") (pintype "input"))
    )
    (net (code "172") (name "unconnected-(U3-FB5-Pad6)") (class "Default")
      (node (ref "U3") (pin "6") (pinfunction "FB5_6") (pintype "input"))
    )
    (net (code "173") (name "unconnected-(U3-PWRGD-Pad20)") (class "Default")
      (node (ref "U3") (pin "20") (pinfunction "PWRGD_20") (pintype "output"))
    )
    (net (code "174") (name "unconnected-(U5-A4-Pad5)") (class "Default")
      (node (ref "U5") (pin "5") (pinfunction "A4_5") (pintype "bidirectional"))
    )
    (net (code "175") (name "unconnected-(U5-B4-Pad10)") (class "Default")
      (node (ref "U5") (pin "10") (pinfunction "B4_10") (pintype "bidirectional"))
    )
    (net (code "176") (name "unconnected-(U5-NC_1-Pad6)") (class "Default")
      (node (ref "U5") (pin "6") (pinfunction "NC_1_6") (pintype "no_connect"))
    )
    (net (code "177") (name "unconnected-(U5-NC_2-Pad9)") (class "Default")
      (node (ref "U5") (pin "9") (pinfunction "NC_2_9") (pintype "no_connect"))
    )
  )
)
